# CrowPanel_Pico_Display-2_8_V1_0_240412.net
KiCad netlist of a schematic drawn in EAGLE
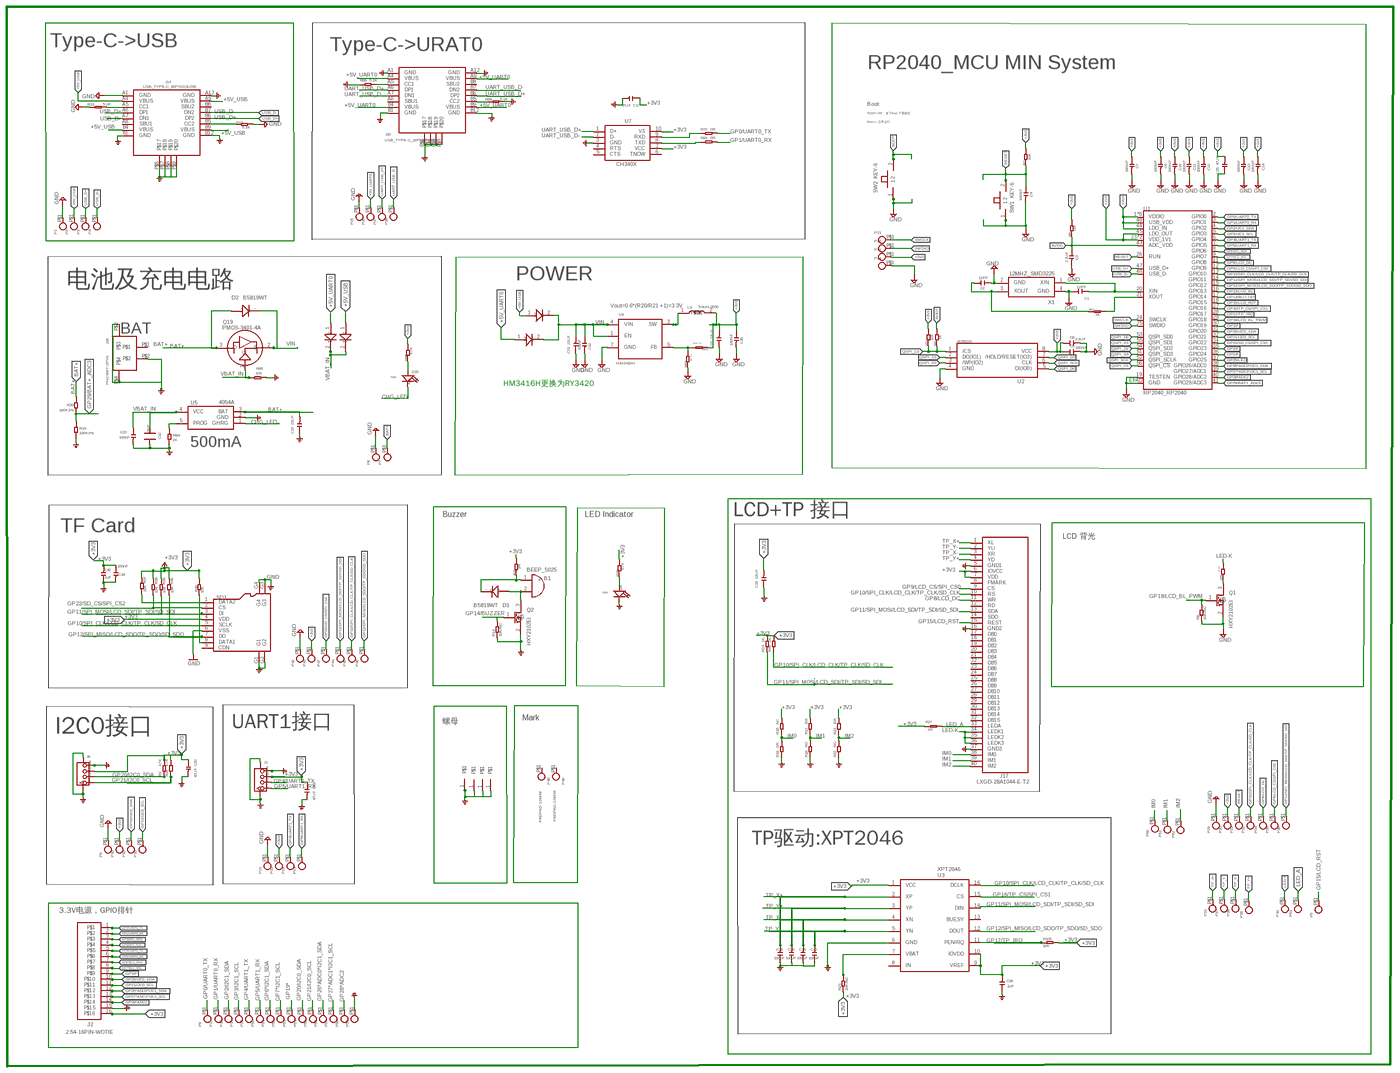
[diagram p0: schematic, sheet 1, overview]
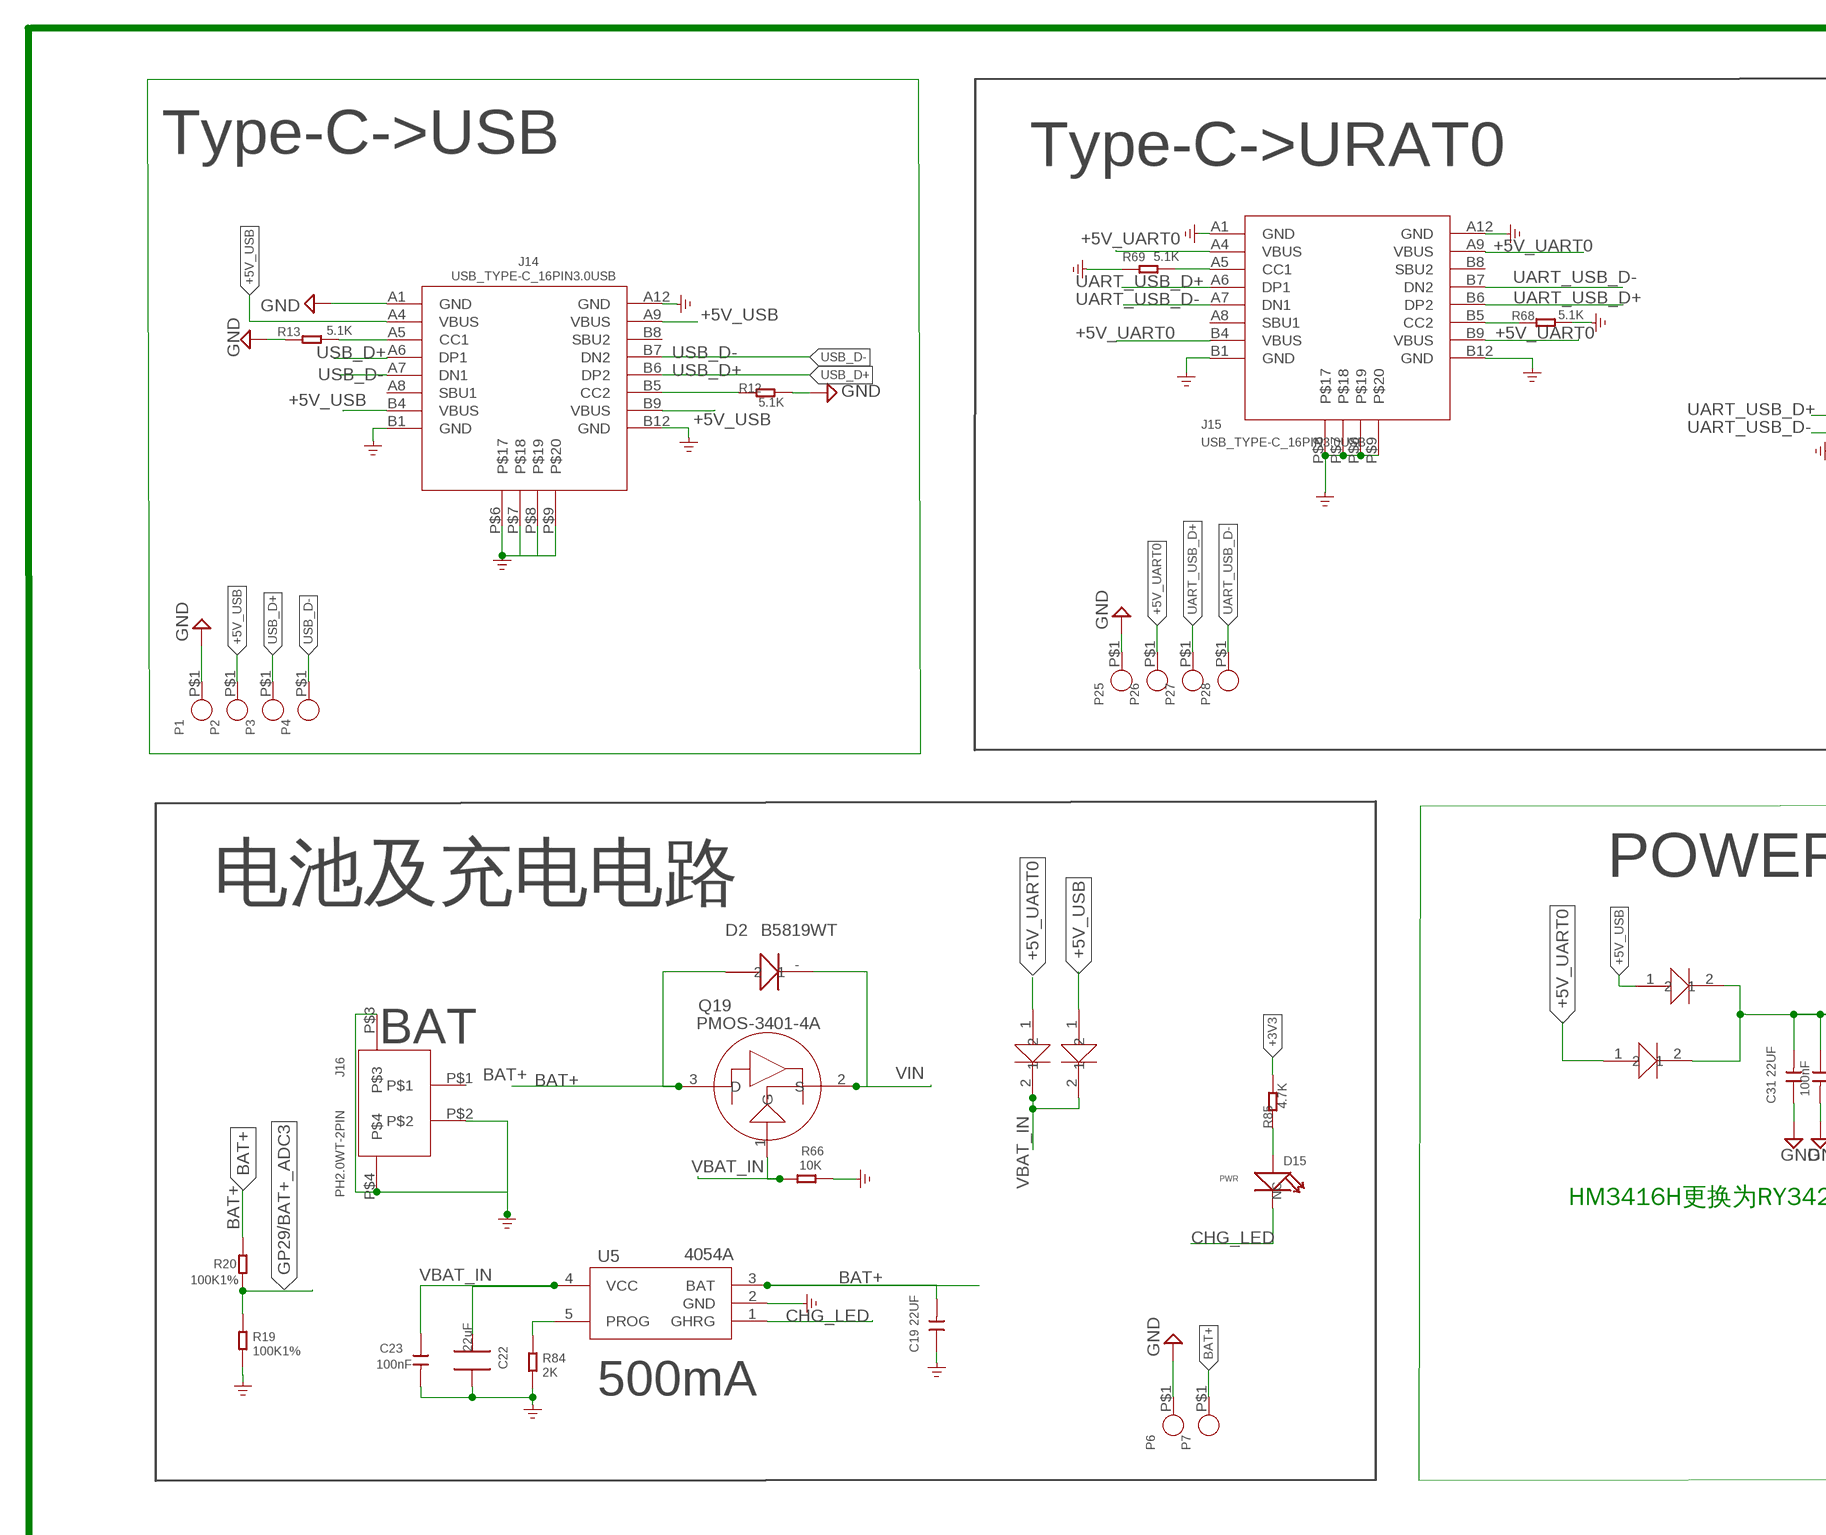
[diagram p1: schematic, sheet 1, part 1 of 4]
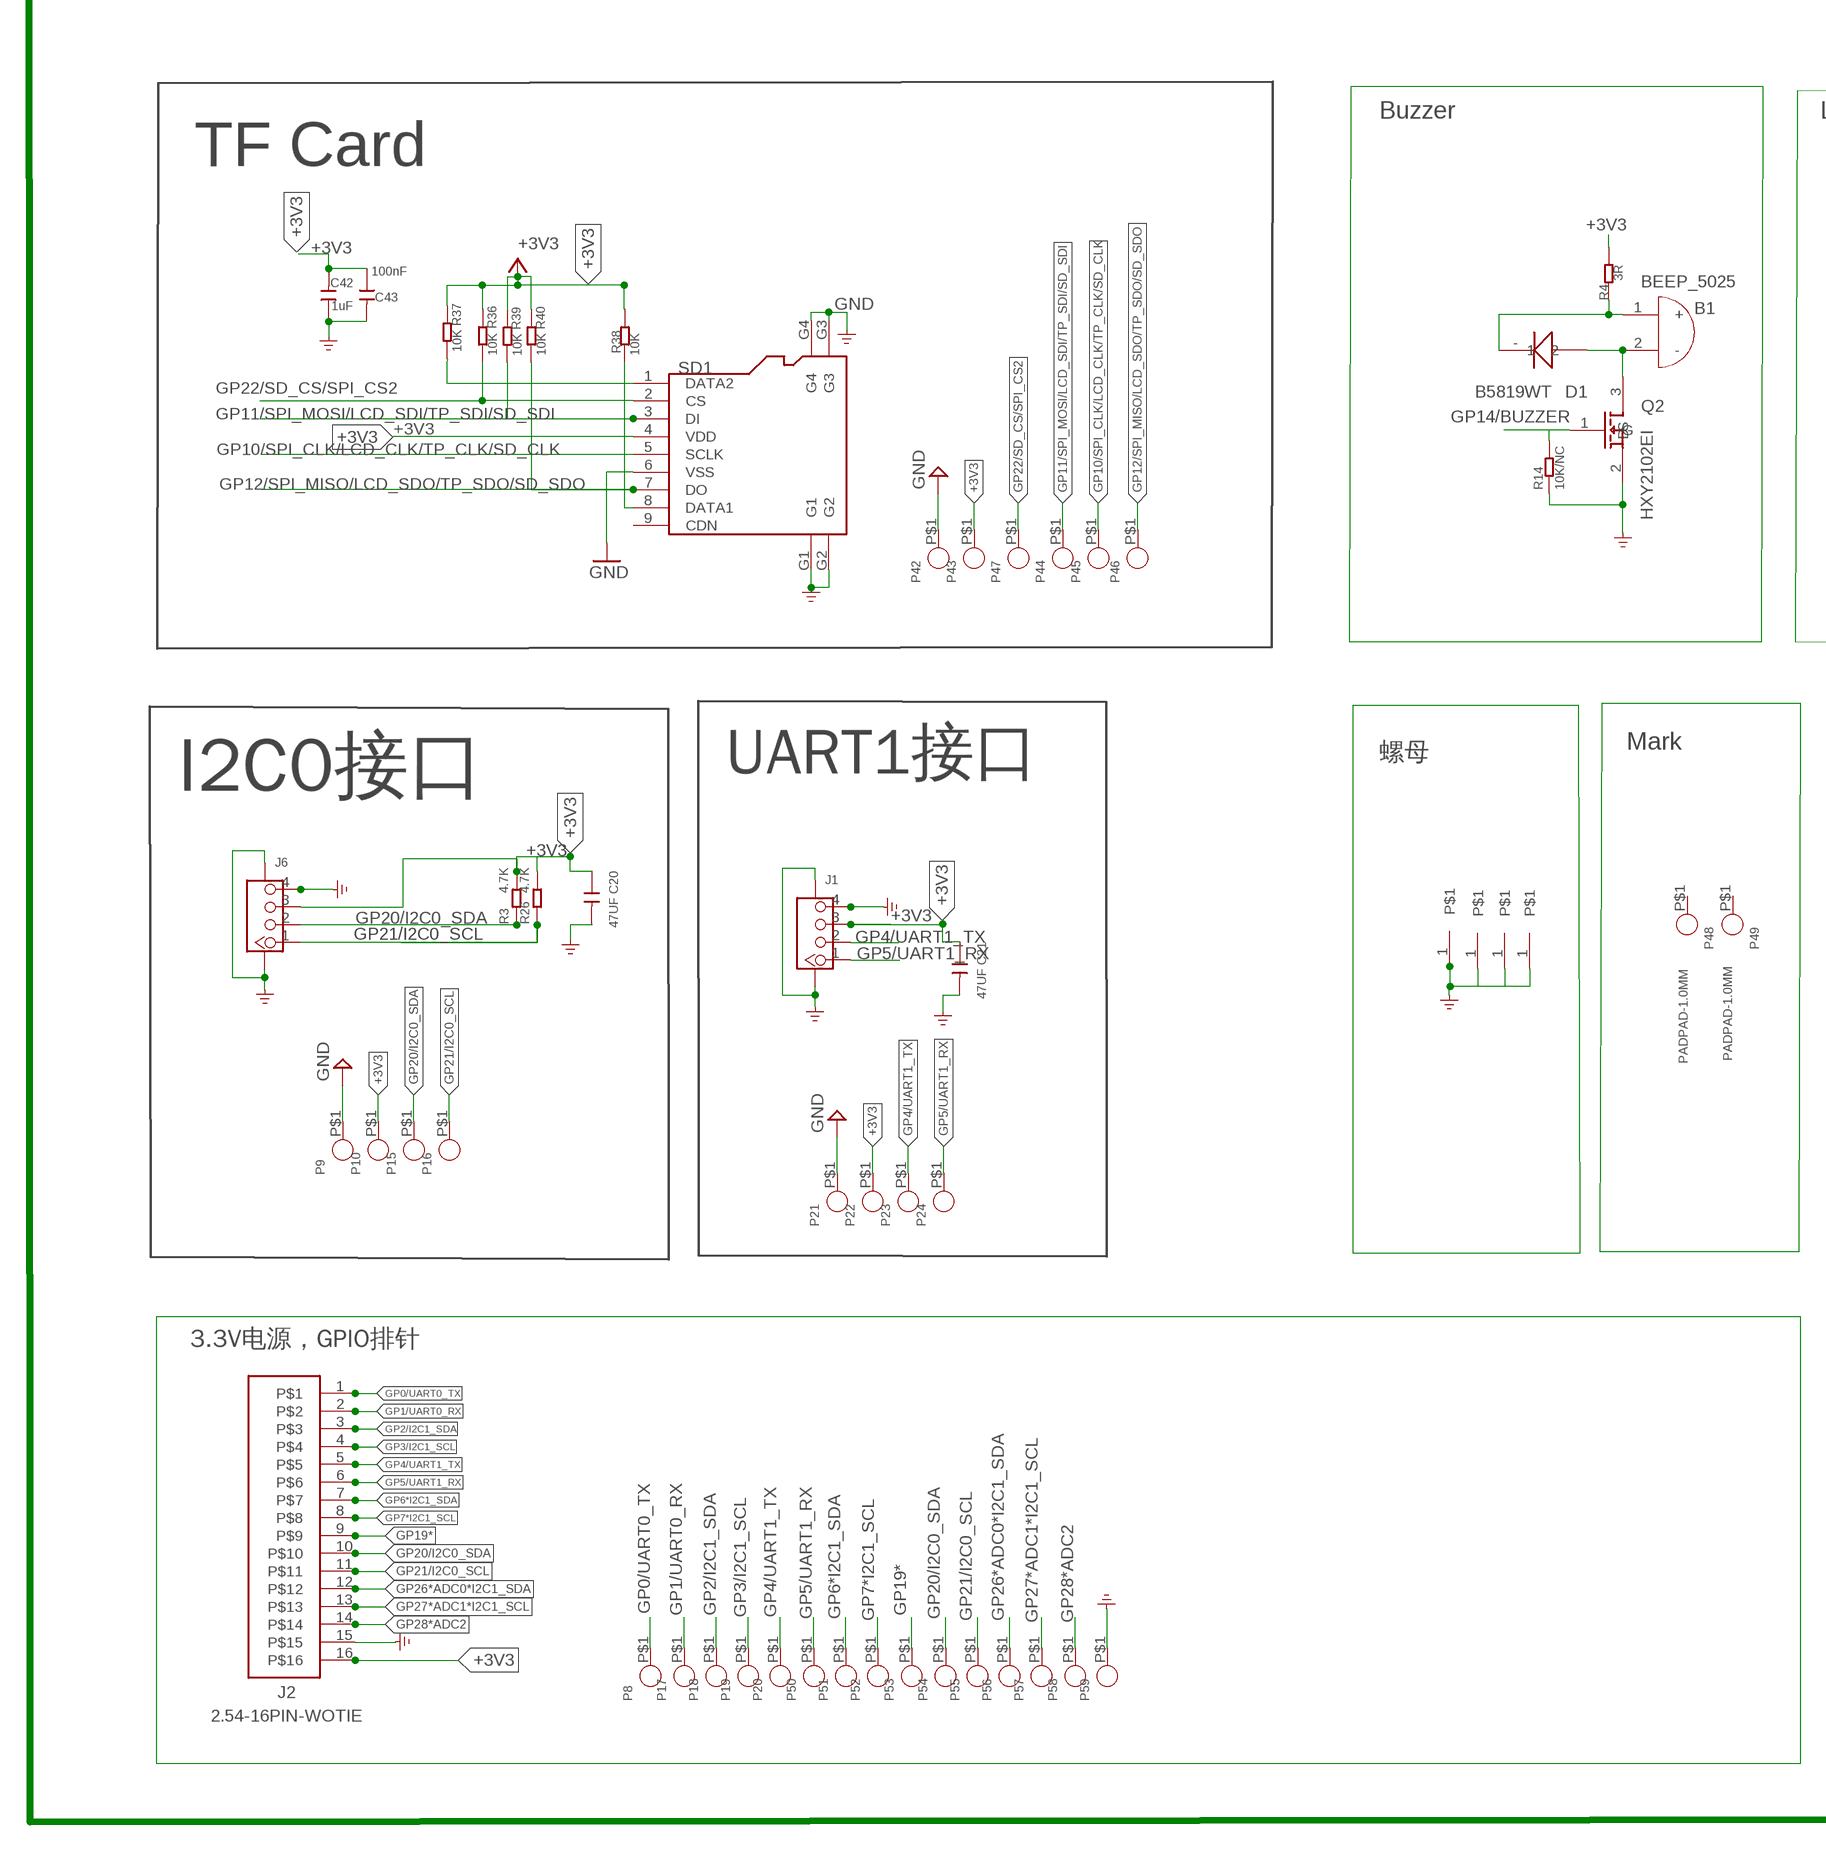
[diagram p2: schematic, sheet 1, part 2 of 4]
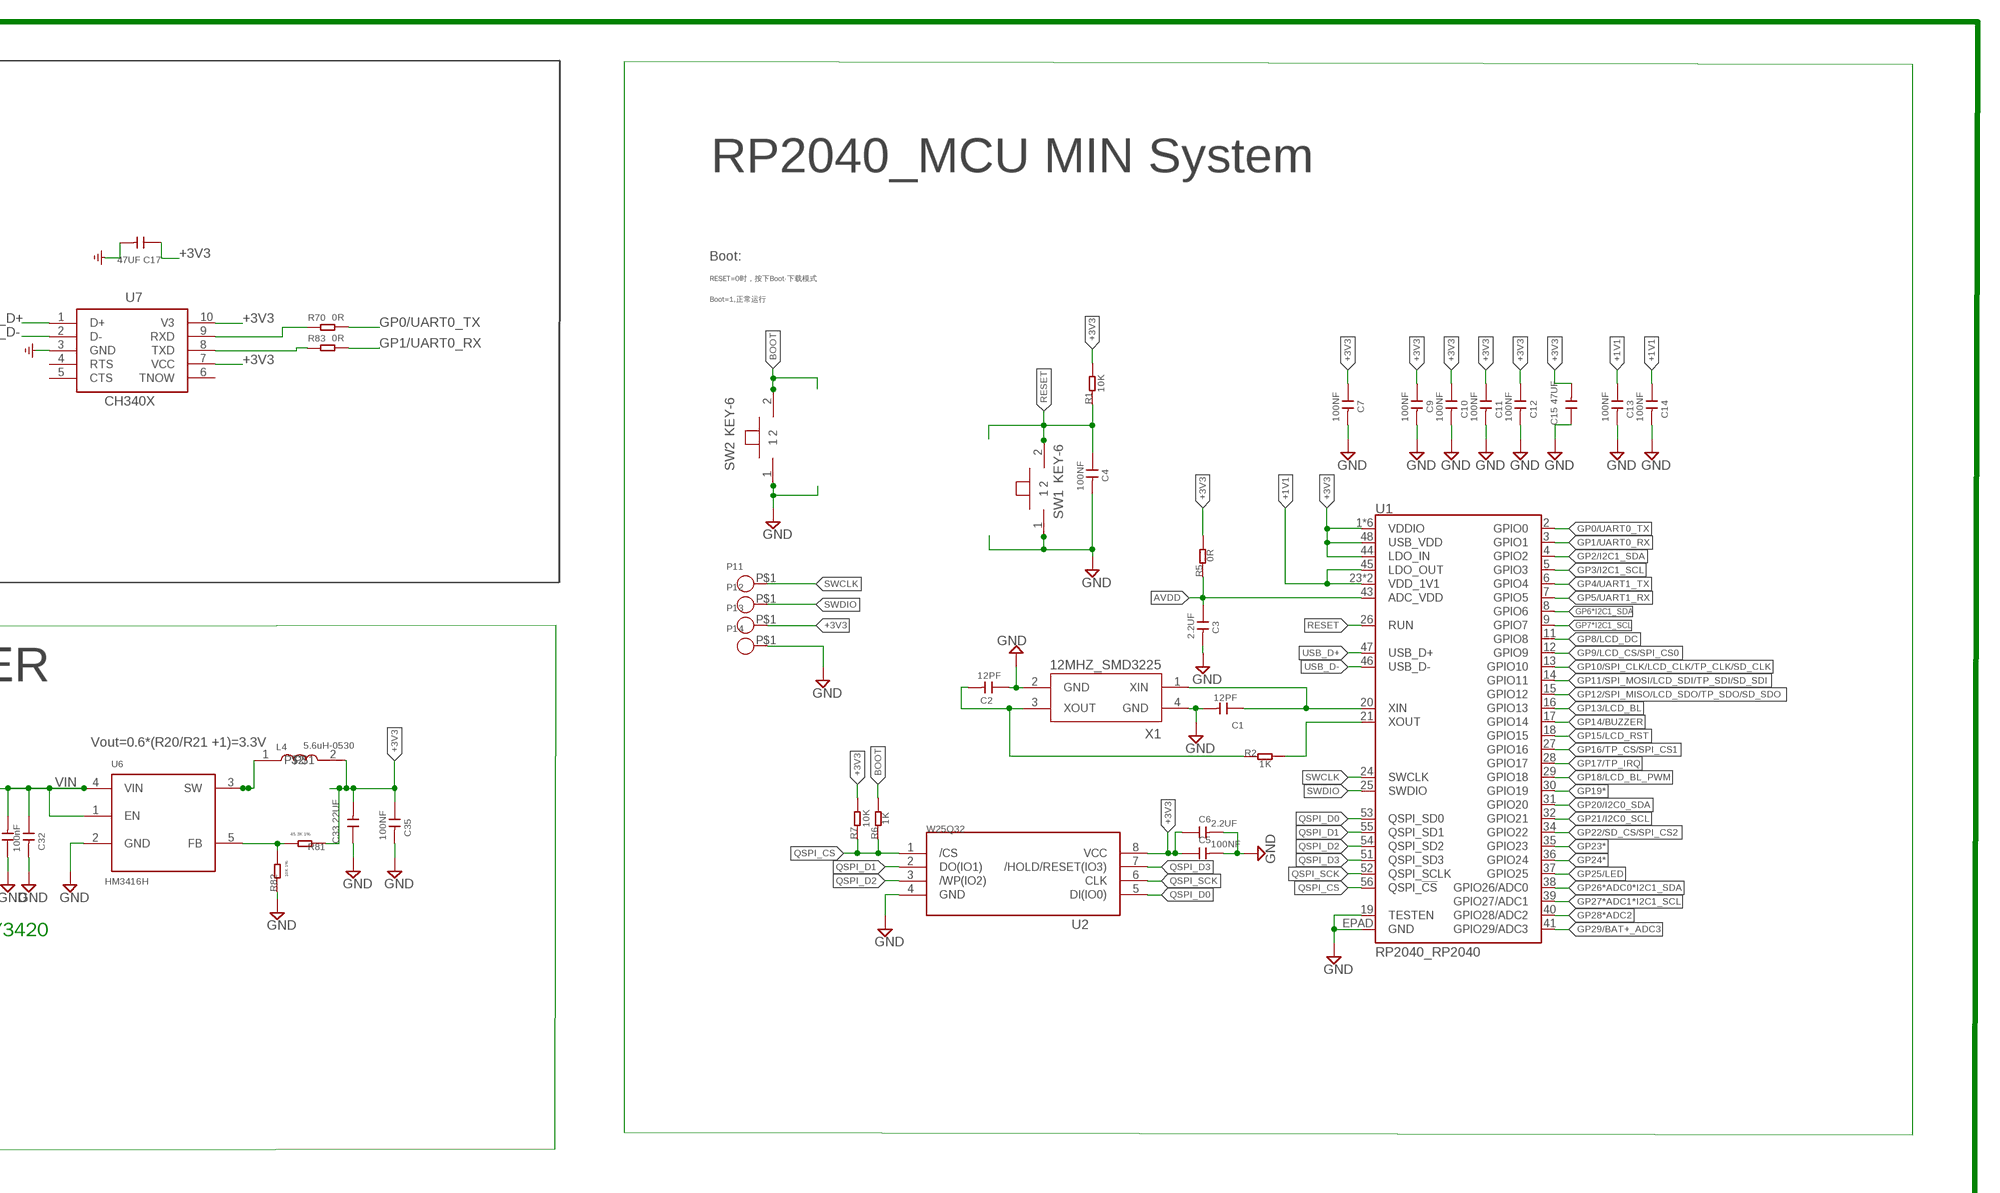
[diagram p3: schematic, sheet 1, part 3 of 4]
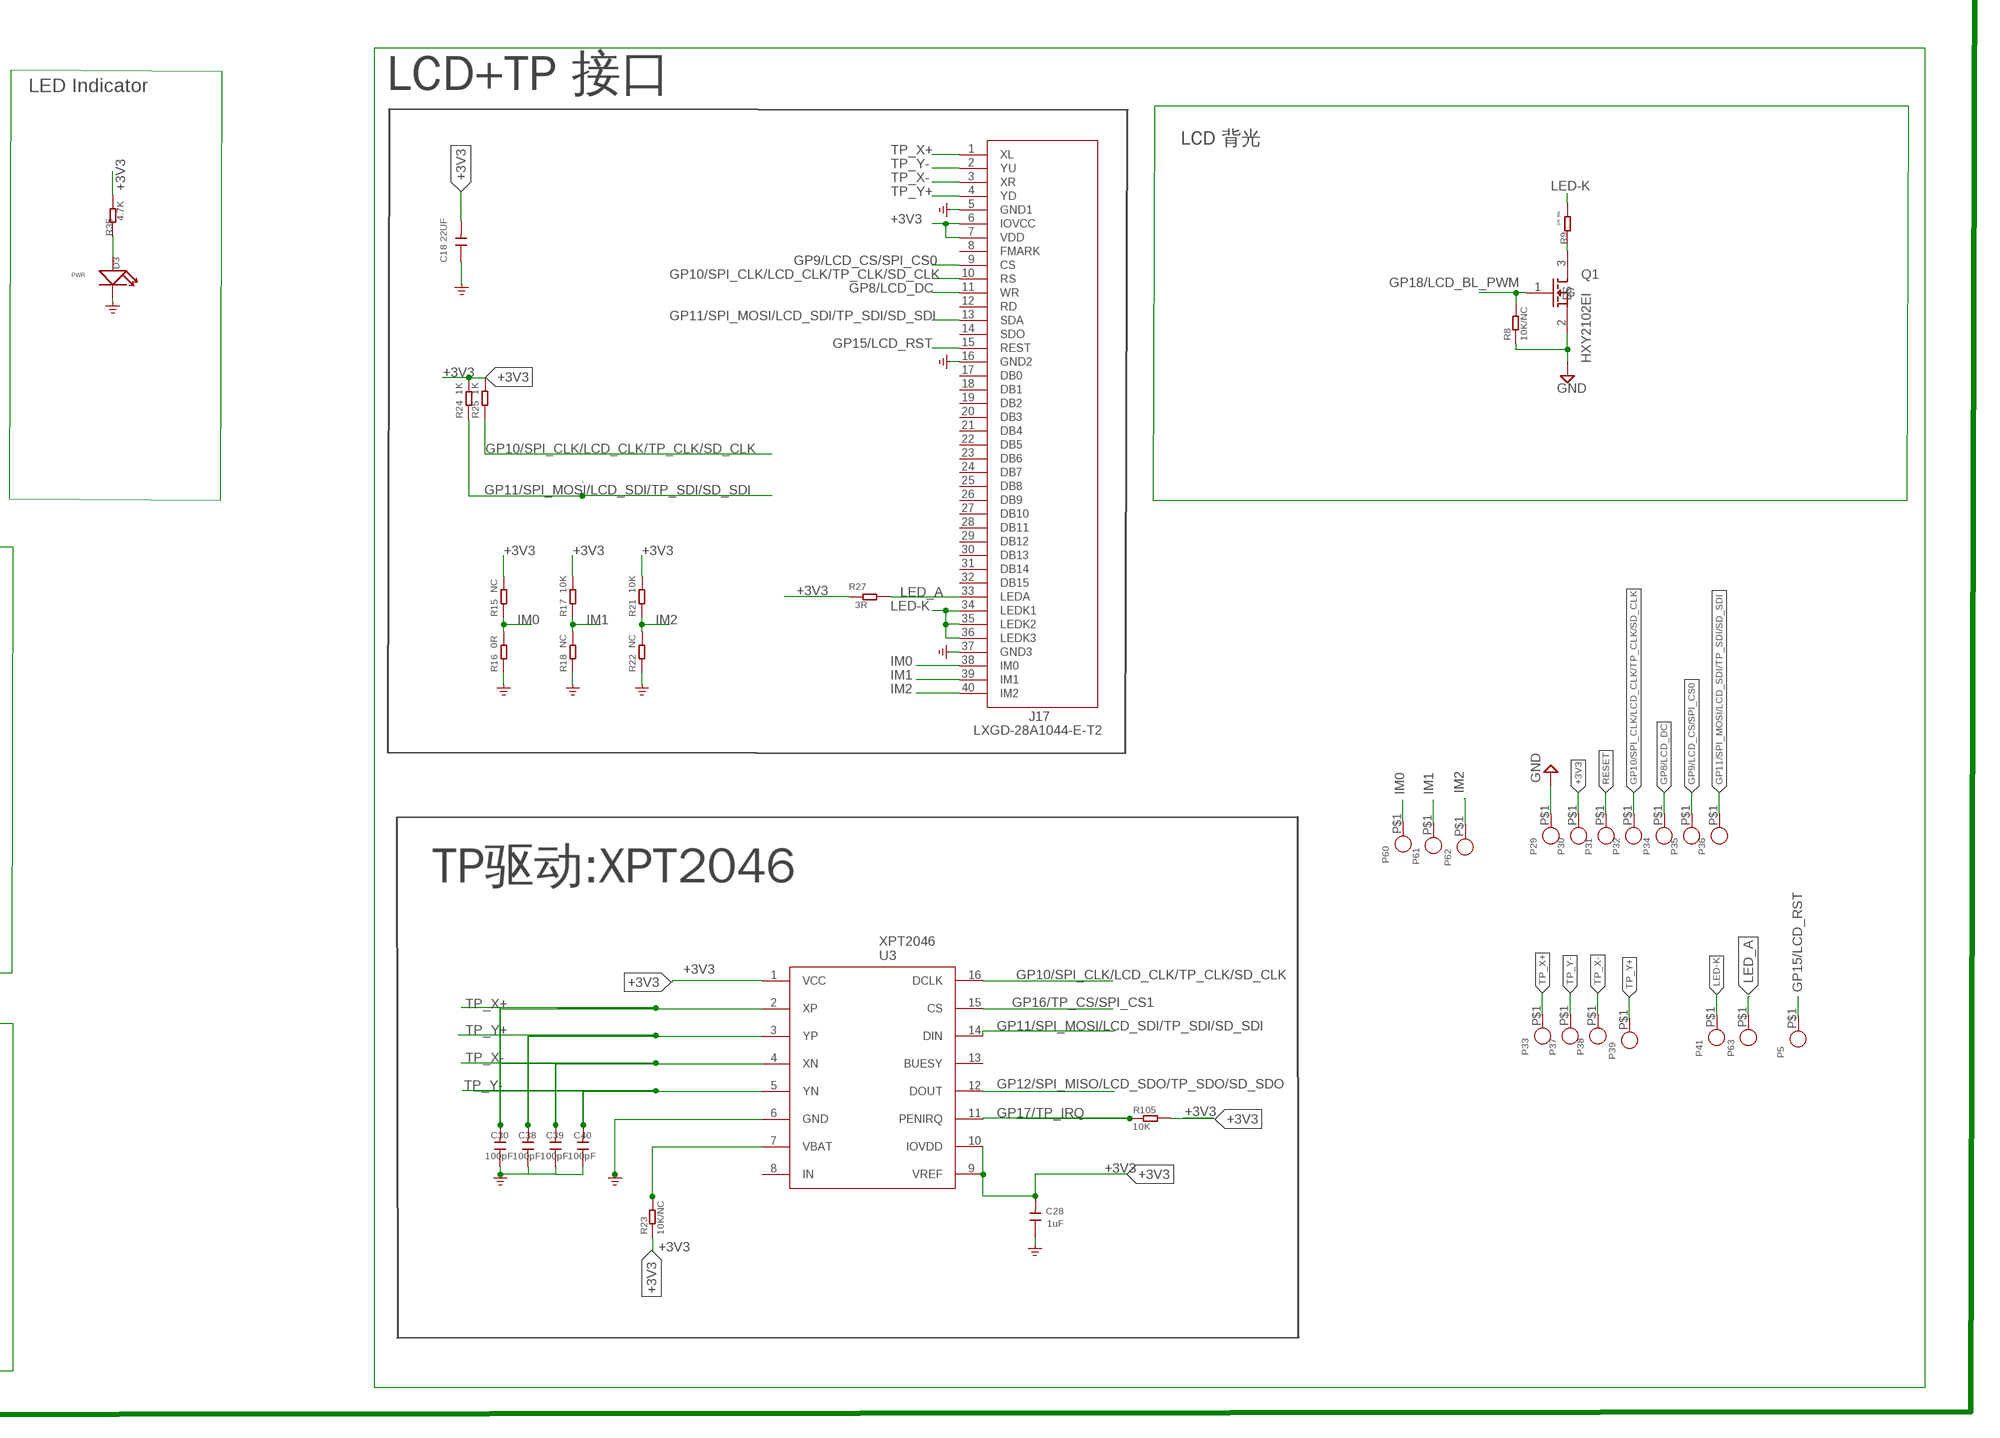
[diagram p4: schematic, sheet 1, part 4 of 4]

(export (version "E")
  (design (tool "Eeschema 10.0.6"))
  (components
    (comp (ref "B1")
      (value "BEEP_5025")
      (footprint "eagle-import:BEEP_5025")
      (libsource (lib "eagle-import") (part "BEEP_5025"))
    )
    (comp (ref "C1")
      (value "12PF")
      (footprint "eagle-import:A_XBJ_0603")
      (libsource (lib "eagle-import") (part "A_XBJ_C0603"))
    )
    (comp (ref "C2")
      (value "12PF")
      (footprint "eagle-import:A_XBJ_0603")
      (libsource (lib "eagle-import") (part "A_XBJ_C0603"))
    )
    (comp (ref "C3")
      (value "2.2UF")
      (footprint "eagle-import:A_XBJ_0603")
      (libsource (lib "eagle-import") (part "A_XBJ_C0603"))
    )
    (comp (ref "C4")
      (value "100NF")
      (footprint "eagle-import:A_XBJ_0603")
      (libsource (lib "eagle-import") (part "A_XBJ_C0603"))
    )
    (comp (ref "C5")
      (value "100NF")
      (footprint "eagle-import:A_XBJ_0603")
      (libsource (lib "eagle-import") (part "A_XBJ_C0603"))
    )
    (comp (ref "C6")
      (value "2.2UF")
      (footprint "eagle-import:A_XBJ_0603")
      (libsource (lib "eagle-import") (part "A_XBJ_C0603"))
    )
    (comp (ref "C7")
      (value "100NF")
      (footprint "eagle-import:A_XBJ_0603")
      (libsource (lib "eagle-import") (part "A_XBJ_C0603"))
    )
    (comp (ref "C9")
      (value "100NF")
      (footprint "eagle-import:A_XBJ_0603")
      (libsource (lib "eagle-import") (part "A_XBJ_C0603"))
    )
    (comp (ref "C10")
      (value "100NF")
      (footprint "eagle-import:A_XBJ_0603")
      (libsource (lib "eagle-import") (part "A_XBJ_C0603"))
    )
    (comp (ref "C11")
      (value "100NF")
      (footprint "eagle-import:A_XBJ_0603")
      (libsource (lib "eagle-import") (part "A_XBJ_C0603"))
    )
    (comp (ref "C12")
      (value "100NF")
      (footprint "eagle-import:A_XBJ_0603")
      (libsource (lib "eagle-import") (part "A_XBJ_C0603"))
    )
    (comp (ref "C13")
      (value "100NF")
      (footprint "eagle-import:A_XBJ_0603")
      (libsource (lib "eagle-import") (part "A_XBJ_C0603"))
    )
    (comp (ref "C14")
      (value "100NF")
      (footprint "eagle-import:A_XBJ_0603")
      (libsource (lib "eagle-import") (part "A_XBJ_C0603"))
    )
    (comp (ref "C15")
      (value "47UF")
      (footprint "eagle-import:A_XBJ_0805")
      (libsource (lib "eagle-import") (part "A_XBJ_C0805"))
    )
    (comp (ref "C17")
      (value "47UF")
      (footprint "eagle-import:A_XBJ_0805")
      (libsource (lib "eagle-import") (part "A_XBJ_C0805"))
    )
    (comp (ref "C18")
      (value "22UF")
      (footprint "eagle-import:A_XBJ_0805")
      (libsource (lib "eagle-import") (part "A_XBJ_C0805"))
    )
    (comp (ref "C19")
      (value "22UF")
      (footprint "eagle-import:A_XBJ_0805")
      (libsource (lib "eagle-import") (part "A_XBJ_C0805"))
    )
    (comp (ref "C20")
      (value "47UF")
      (footprint "eagle-import:A_XBJ_0805")
      (libsource (lib "eagle-import") (part "A_XBJ_C0805"))
    )
    (comp (ref "C21")
      (value "47UF")
      (footprint "eagle-import:A_XBJ_0805")
      (libsource (lib "eagle-import") (part "A_XBJ_C0805"))
    )
    (comp (ref "C22")
      (value "22uF")
      (footprint "eagle-import:0805_S")
      (libsource (lib "eagle-import") (part "C0805_S"))
    )
    (comp (ref "C23")
      (value "100nF")
      (footprint "eagle-import:C0603")
      (libsource (lib "eagle-import") (part "C-0603"))
    )
    (comp (ref "C28")
      (value "1uF")
      (footprint "eagle-import:DISCRETE_C0603")
      (libsource (lib "eagle-import") (part "DISCRETE_C-0603"))
    )
    (comp (ref "C30")
      (value "100pF")
      (footprint "eagle-import:0603")
      (libsource (lib "eagle-import") (part "C0603"))
    )
    (comp (ref "C31")
      (value "22UF")
      (footprint "eagle-import:A_XBJ_0805")
      (libsource (lib "eagle-import") (part "A_XBJ_C0805"))
    )
    (comp (ref "C32")
      (value "100nF")
      (footprint "eagle-import:A_XBJ_0603")
      (libsource (lib "eagle-import") (part "A_XBJ_C0603"))
    )
    (comp (ref "C33")
      (value "22UF")
      (footprint "eagle-import:A_XBJ_0805")
      (libsource (lib "eagle-import") (part "A_XBJ_C0805"))
    )
    (comp (ref "C35")
      (value "100NF")
      (footprint "eagle-import:A_XBJ_0603")
      (libsource (lib "eagle-import") (part "A_XBJ_C0603"))
    )
    (comp (ref "C38")
      (value "100pF")
      (footprint "eagle-import:0603")
      (libsource (lib "eagle-import") (part "C0603"))
    )
    (comp (ref "C39")
      (value "100pF")
      (footprint "eagle-import:0603")
      (libsource (lib "eagle-import") (part "C0603"))
    )
    (comp (ref "C40")
      (value "100pF")
      (footprint "eagle-import:0603")
      (libsource (lib "eagle-import") (part "C0603"))
    )
    (comp (ref "C42")
      (value "1uF")
      (footprint "eagle-import:DISCRETE_C0603")
      (libsource (lib "eagle-import") (part "DISCRETE_C-0603"))
    )
    (comp (ref "C43")
      (value "100nF")
      (footprint "eagle-import:C0603")
      (libsource (lib "eagle-import") (part "C-0603"))
    )
    (comp (ref "D1")
      (value "B5819WT")
      (footprint "eagle-import:SOD-523")
      (libsource (lib "eagle-import") (part "DIODE_W"))
    )
    (comp (ref "D2")
      (value "B5819WT")
      (footprint "eagle-import:SOD-523")
      (libsource (lib "eagle-import") (part "DIODE_W"))
    )
    (comp (ref "D3")
      (value "DISCRETE_007-LED0603")
      (footprint "eagle-import:DISCRETE_D0603")
      (libsource (lib "eagle-import") (part "DISCRETE_007-LED0603"))
    )
    (comp (ref "D4")
      (value "SOD-323")
      (footprint "eagle-import:SOD-323")
      (libsource (lib "eagle-import") (part "SOD-323"))
    )
    (comp (ref "D5")
      (value "SOD-323")
      (footprint "eagle-import:SOD-323")
      (libsource (lib "eagle-import") (part "SOD-323"))
    )
    (comp (ref "D6")
      (value "SOD-323")
      (footprint "eagle-import:SOD-323")
      (libsource (lib "eagle-import") (part "SOD-323"))
    )
    (comp (ref "D8")
      (value "SOD-323")
      (footprint "eagle-import:SOD-323")
      (libsource (lib "eagle-import") (part "SOD-323"))
    )
    (comp (ref "D15")
      (value "NC")
      (footprint "eagle-import:DISCRETE_D0603")
      (libsource (lib "eagle-import") (part "DISCRETE_007-LED0603"))
    )
    (comp (ref "J1")
      (value "CONNECTOR_TWIG-4P-2.0-SMD-FEMALE-REINFORCE90D")
      (footprint "eagle-import:CONNECTOR_4P-SMD-2.0-90D")
      (libsource (lib "eagle-import") (part "CONNECTOR_TWIG-4P-2.0-SMD-FEMALE-REINFORCE90D"))
    )
    (comp (ref "J2")
      (value "2.54-16PIN-WOTIE")
      (footprint "eagle-import:2.54-16P-WOTIE")
      (libsource (lib "eagle-import") (part "2.54-16PIN-WOTIE"))
    )
    (comp (ref "J6")
      (value "CONNECTOR_TWIG-4P-2.0-SMD-FEMALE-REINFORCE90D")
      (footprint "eagle-import:CONNECTOR_4P-SMD-2.0-90D")
      (libsource (lib "eagle-import") (part "CONNECTOR_TWIG-4P-2.0-SMD-FEMALE-REINFORCE90D"))
    )
    (comp (ref "J14")
      (value "USB_TYPE-C_16PIN3.0USB")
      (footprint "eagle-import:KEVIN_3.0TYPEC-SMD")
      (libsource (lib "eagle-import") (part "USB_TYPE-C_16PIN3.0USB"))
    )
    (comp (ref "J15")
      (value "USB_TYPE-C_16PIN3.0USB")
      (footprint "eagle-import:KEVIN_3.0TYPEC-SMD")
      (libsource (lib "eagle-import") (part "USB_TYPE-C_16PIN3.0USB"))
    )
    (comp (ref "J16")
      (value "PH2.0WT-2PIN")
      (footprint "eagle-import:PH2.0WT-2PIN")
      (libsource (lib "eagle-import") (part "PH2.0WT-2PIN"))
    )
    (comp (ref "J17")
      (value "LXGD-28A1044-E-T2")
      (footprint "eagle-import:40PIN-0.5MM")
      (libsource (lib "eagle-import") (part "LXGD-28A1044-E-T2"))
    )
    (comp (ref "L4")
      (value "5.6uH-0530")
      (footprint "eagle-import:CD54_CD54")
      (libsource (lib "eagle-import") (part "L-0530"))
    )
    (comp (ref "P1")
      (value "CROWPI_POW_PADPAD-1.0MM")
      (footprint "eagle-import:CROWPI_POW_PAD-1.0MM")
      (libsource (lib "eagle-import") (part "CROWPI_POW_PADPAD-1.0MM"))
    )
    (comp (ref "P2")
      (value "CROWPI_POW_PADPAD-1.0MM")
      (footprint "eagle-import:CROWPI_POW_PAD-1.0MM")
      (libsource (lib "eagle-import") (part "CROWPI_POW_PADPAD-1.0MM"))
    )
    (comp (ref "P3")
      (value "CROWPI_POW_PADPAD-1.0MM")
      (footprint "eagle-import:CROWPI_POW_PAD-1.0MM")
      (libsource (lib "eagle-import") (part "CROWPI_POW_PADPAD-1.0MM"))
    )
    (comp (ref "P4")
      (value "CROWPI_POW_PADPAD-1.0MM")
      (footprint "eagle-import:CROWPI_POW_PAD-1.0MM")
      (libsource (lib "eagle-import") (part "CROWPI_POW_PADPAD-1.0MM"))
    )
    (comp (ref "P5")
      (value "CROWPI_POW_PADPAD-1.0MM")
      (footprint "eagle-import:CROWPI_POW_PAD-1.0MM")
      (libsource (lib "eagle-import") (part "CROWPI_POW_PADPAD-1.0MM"))
    )
    (comp (ref "P6")
      (value "CROWPI_POW_PADPAD-1.0MM")
      (footprint "eagle-import:CROWPI_POW_PAD-1.0MM")
      (libsource (lib "eagle-import") (part "CROWPI_POW_PADPAD-1.0MM"))
    )
    (comp (ref "P7")
      (value "CROWPI_POW_PADPAD-1.0MM")
      (footprint "eagle-import:CROWPI_POW_PAD-1.0MM")
      (libsource (lib "eagle-import") (part "CROWPI_POW_PADPAD-1.0MM"))
    )
    (comp (ref "P8")
      (value "CROWPI_POW_PADPAD-1.0MM")
      (footprint "eagle-import:CROWPI_POW_PAD-1.0MM")
      (libsource (lib "eagle-import") (part "CROWPI_POW_PADPAD-1.0MM"))
    )
    (comp (ref "P9")
      (value "CROWPI_POW_PADPAD-1.0MM")
      (footprint "eagle-import:CROWPI_POW_PAD-1.0MM")
      (libsource (lib "eagle-import") (part "CROWPI_POW_PADPAD-1.0MM"))
    )
    (comp (ref "P10")
      (value "CROWPI_POW_PADPAD-1.0MM")
      (footprint "eagle-import:CROWPI_POW_PAD-1.0MM")
      (libsource (lib "eagle-import") (part "CROWPI_POW_PADPAD-1.0MM"))
    )
    (comp (ref "P11")
      (value "CROWPI_POW_PADPAD-1.0MM")
      (footprint "eagle-import:CROWPI_POW_PAD-1.0MM")
      (libsource (lib "eagle-import") (part "CROWPI_POW_PADPAD-1.0MM"))
    )
    (comp (ref "P12")
      (value "CROWPI_POW_PADPAD-1.0MM")
      (footprint "eagle-import:CROWPI_POW_PAD-1.0MM")
      (libsource (lib "eagle-import") (part "CROWPI_POW_PADPAD-1.0MM"))
    )
    (comp (ref "P13")
      (value "CROWPI_POW_PADPAD-1.0MM")
      (footprint "eagle-import:CROWPI_POW_PAD-1.0MM")
      (libsource (lib "eagle-import") (part "CROWPI_POW_PADPAD-1.0MM"))
    )
    (comp (ref "P14")
      (value "CROWPI_POW_PADPAD-1.0MM")
      (footprint "eagle-import:CROWPI_POW_PAD-1.0MM")
      (libsource (lib "eagle-import") (part "CROWPI_POW_PADPAD-1.0MM"))
    )
    (comp (ref "P15")
      (value "CROWPI_POW_PADPAD-1.0MM")
      (footprint "eagle-import:CROWPI_POW_PAD-1.0MM")
      (libsource (lib "eagle-import") (part "CROWPI_POW_PADPAD-1.0MM"))
    )
    (comp (ref "P16")
      (value "CROWPI_POW_PADPAD-1.0MM")
      (footprint "eagle-import:CROWPI_POW_PAD-1.0MM")
      (libsource (lib "eagle-import") (part "CROWPI_POW_PADPAD-1.0MM"))
    )
    (comp (ref "P17")
      (value "CROWPI_POW_PADPAD-1.0MM")
      (footprint "eagle-import:CROWPI_POW_PAD-1.0MM")
      (libsource (lib "eagle-import") (part "CROWPI_POW_PADPAD-1.0MM"))
    )
    (comp (ref "P18")
      (value "CROWPI_POW_PADPAD-1.0MM")
      (footprint "eagle-import:CROWPI_POW_PAD-1.0MM")
      (libsource (lib "eagle-import") (part "CROWPI_POW_PADPAD-1.0MM"))
    )
    (comp (ref "P19")
      (value "CROWPI_POW_PADPAD-1.0MM")
      (footprint "eagle-import:CROWPI_POW_PAD-1.0MM")
      (libsource (lib "eagle-import") (part "CROWPI_POW_PADPAD-1.0MM"))
    )
    (comp (ref "P20")
      (value "CROWPI_POW_PADPAD-1.0MM")
      (footprint "eagle-import:CROWPI_POW_PAD-1.0MM")
      (libsource (lib "eagle-import") (part "CROWPI_POW_PADPAD-1.0MM"))
    )
    (comp (ref "P21")
      (value "CROWPI_POW_PADPAD-1.0MM")
      (footprint "eagle-import:CROWPI_POW_PAD-1.0MM")
      (libsource (lib "eagle-import") (part "CROWPI_POW_PADPAD-1.0MM"))
    )
    (comp (ref "P22")
      (value "CROWPI_POW_PADPAD-1.0MM")
      (footprint "eagle-import:CROWPI_POW_PAD-1.0MM")
      (libsource (lib "eagle-import") (part "CROWPI_POW_PADPAD-1.0MM"))
    )
    (comp (ref "P23")
      (value "CROWPI_POW_PADPAD-1.0MM")
      (footprint "eagle-import:CROWPI_POW_PAD-1.0MM")
      (libsource (lib "eagle-import") (part "CROWPI_POW_PADPAD-1.0MM"))
    )
    (comp (ref "P24")
      (value "CROWPI_POW_PADPAD-1.0MM")
      (footprint "eagle-import:CROWPI_POW_PAD-1.0MM")
      (libsource (lib "eagle-import") (part "CROWPI_POW_PADPAD-1.0MM"))
    )
    (comp (ref "P25")
      (value "CROWPI_POW_PADPAD-1.0MM")
      (footprint "eagle-import:CROWPI_POW_PAD-1.0MM")
      (libsource (lib "eagle-import") (part "CROWPI_POW_PADPAD-1.0MM"))
    )
    (comp (ref "P26")
      (value "CROWPI_POW_PADPAD-1.0MM")
      (footprint "eagle-import:CROWPI_POW_PAD-1.0MM")
      (libsource (lib "eagle-import") (part "CROWPI_POW_PADPAD-1.0MM"))
    )
    (comp (ref "P27")
      (value "CROWPI_POW_PADPAD-1.0MM")
      (footprint "eagle-import:CROWPI_POW_PAD-1.0MM")
      (libsource (lib "eagle-import") (part "CROWPI_POW_PADPAD-1.0MM"))
    )
    (comp (ref "P28")
      (value "CROWPI_POW_PADPAD-1.0MM")
      (footprint "eagle-import:CROWPI_POW_PAD-1.0MM")
      (libsource (lib "eagle-import") (part "CROWPI_POW_PADPAD-1.0MM"))
    )
    (comp (ref "P29")
      (value "CROWPI_POW_PADPAD-1.0MM")
      (footprint "eagle-import:CROWPI_POW_PAD-1.0MM")
      (libsource (lib "eagle-import") (part "CROWPI_POW_PADPAD-1.0MM"))
    )
    (comp (ref "P30")
      (value "CROWPI_POW_PADPAD-1.0MM")
      (footprint "eagle-import:CROWPI_POW_PAD-1.0MM")
      (libsource (lib "eagle-import") (part "CROWPI_POW_PADPAD-1.0MM"))
    )
    (comp (ref "P31")
      (value "CROWPI_POW_PADPAD-1.0MM")
      (footprint "eagle-import:CROWPI_POW_PAD-1.0MM")
      (libsource (lib "eagle-import") (part "CROWPI_POW_PADPAD-1.0MM"))
    )
    (comp (ref "P32")
      (value "CROWPI_POW_PADPAD-1.0MM")
      (footprint "eagle-import:CROWPI_POW_PAD-1.0MM")
      (libsource (lib "eagle-import") (part "CROWPI_POW_PADPAD-1.0MM"))
    )
    (comp (ref "P33")
      (value "CROWPI_POW_PADPAD-1.0MM")
      (footprint "eagle-import:CROWPI_POW_PAD-1.0MM")
      (libsource (lib "eagle-import") (part "CROWPI_POW_PADPAD-1.0MM"))
    )
    (comp (ref "P34")
      (value "CROWPI_POW_PADPAD-1.0MM")
      (footprint "eagle-import:CROWPI_POW_PAD-1.0MM")
      (libsource (lib "eagle-import") (part "CROWPI_POW_PADPAD-1.0MM"))
    )
    (comp (ref "P35")
      (value "CROWPI_POW_PADPAD-1.0MM")
      (footprint "eagle-import:CROWPI_POW_PAD-1.0MM")
      (libsource (lib "eagle-import") (part "CROWPI_POW_PADPAD-1.0MM"))
    )
    (comp (ref "P36")
      (value "CROWPI_POW_PADPAD-1.0MM")
      (footprint "eagle-import:CROWPI_POW_PAD-1.0MM")
      (libsource (lib "eagle-import") (part "CROWPI_POW_PADPAD-1.0MM"))
    )
    (comp (ref "P37")
      (value "CROWPI_POW_PADPAD-1.0MM")
      (footprint "eagle-import:CROWPI_POW_PAD-1.0MM")
      (libsource (lib "eagle-import") (part "CROWPI_POW_PADPAD-1.0MM"))
    )
    (comp (ref "P38")
      (value "CROWPI_POW_PADPAD-1.0MM")
      (footprint "eagle-import:CROWPI_POW_PAD-1.0MM")
      (libsource (lib "eagle-import") (part "CROWPI_POW_PADPAD-1.0MM"))
    )
    (comp (ref "P39")
      (value "CROWPI_POW_PADPAD-1.0MM")
      (footprint "eagle-import:CROWPI_POW_PAD-1.0MM")
      (libsource (lib "eagle-import") (part "CROWPI_POW_PADPAD-1.0MM"))
    )
    (comp (ref "P41")
      (value "CROWPI_POW_PADPAD-1.0MM")
      (footprint "eagle-import:CROWPI_POW_PAD-1.0MM")
      (libsource (lib "eagle-import") (part "CROWPI_POW_PADPAD-1.0MM"))
    )
    (comp (ref "P42")
      (value "CROWPI_POW_PADPAD-1.0MM")
      (footprint "eagle-import:CROWPI_POW_PAD-1.0MM")
      (libsource (lib "eagle-import") (part "CROWPI_POW_PADPAD-1.0MM"))
    )
    (comp (ref "P43")
      (value "CROWPI_POW_PADPAD-1.0MM")
      (footprint "eagle-import:CROWPI_POW_PAD-1.0MM")
      (libsource (lib "eagle-import") (part "CROWPI_POW_PADPAD-1.0MM"))
    )
    (comp (ref "P44")
      (value "CROWPI_POW_PADPAD-1.0MM")
      (footprint "eagle-import:CROWPI_POW_PAD-1.0MM")
      (libsource (lib "eagle-import") (part "CROWPI_POW_PADPAD-1.0MM"))
    )
    (comp (ref "P45")
      (value "CROWPI_POW_PADPAD-1.0MM")
      (footprint "eagle-import:CROWPI_POW_PAD-1.0MM")
      (libsource (lib "eagle-import") (part "CROWPI_POW_PADPAD-1.0MM"))
    )
    (comp (ref "P46")
      (value "CROWPI_POW_PADPAD-1.0MM")
      (footprint "eagle-import:CROWPI_POW_PAD-1.0MM")
      (libsource (lib "eagle-import") (part "CROWPI_POW_PADPAD-1.0MM"))
    )
    (comp (ref "P47")
      (value "CROWPI_POW_PADPAD-1.0MM")
      (footprint "eagle-import:CROWPI_POW_PAD-1.0MM")
      (libsource (lib "eagle-import") (part "CROWPI_POW_PADPAD-1.0MM"))
    )
    (comp (ref "P48")
      (value "PADPAD-1.0MM")
      (footprint "eagle-import:PAD-1.0MM")
      (libsource (lib "eagle-import") (part "PADPAD-1.0MM"))
    )
    (comp (ref "P49")
      (value "PADPAD-1.0MM")
      (footprint "eagle-import:PAD-1.0MM")
      (libsource (lib "eagle-import") (part "PADPAD-1.0MM"))
    )
    (comp (ref "P50")
      (value "CROWPI_POW_PADPAD-1.0MM")
      (footprint "eagle-import:CROWPI_POW_PAD-1.0MM")
      (libsource (lib "eagle-import") (part "CROWPI_POW_PADPAD-1.0MM"))
    )
    (comp (ref "P51")
      (value "CROWPI_POW_PADPAD-1.0MM")
      (footprint "eagle-import:CROWPI_POW_PAD-1.0MM")
      (libsource (lib "eagle-import") (part "CROWPI_POW_PADPAD-1.0MM"))
    )
    (comp (ref "P52")
      (value "CROWPI_POW_PADPAD-1.0MM")
      (footprint "eagle-import:CROWPI_POW_PAD-1.0MM")
      (libsource (lib "eagle-import") (part "CROWPI_POW_PADPAD-1.0MM"))
    )
    (comp (ref "P53")
      (value "CROWPI_POW_PADPAD-1.0MM")
      (footprint "eagle-import:CROWPI_POW_PAD-1.0MM")
      (libsource (lib "eagle-import") (part "CROWPI_POW_PADPAD-1.0MM"))
    )
    (comp (ref "P54")
      (value "CROWPI_POW_PADPAD-1.0MM")
      (footprint "eagle-import:CROWPI_POW_PAD-1.0MM")
      (libsource (lib "eagle-import") (part "CROWPI_POW_PADPAD-1.0MM"))
    )
    (comp (ref "P55")
      (value "CROWPI_POW_PADPAD-1.0MM")
      (footprint "eagle-import:CROWPI_POW_PAD-1.0MM")
      (libsource (lib "eagle-import") (part "CROWPI_POW_PADPAD-1.0MM"))
    )
    (comp (ref "P56")
      (value "CROWPI_POW_PADPAD-1.0MM")
      (footprint "eagle-import:CROWPI_POW_PAD-1.0MM")
      (libsource (lib "eagle-import") (part "CROWPI_POW_PADPAD-1.0MM"))
    )
    (comp (ref "P57")
      (value "CROWPI_POW_PADPAD-1.0MM")
      (footprint "eagle-import:CROWPI_POW_PAD-1.0MM")
      (libsource (lib "eagle-import") (part "CROWPI_POW_PADPAD-1.0MM"))
    )
    (comp (ref "P58")
      (value "CROWPI_POW_PADPAD-1.0MM")
      (footprint "eagle-import:CROWPI_POW_PAD-1.0MM")
      (libsource (lib "eagle-import") (part "CROWPI_POW_PADPAD-1.0MM"))
    )
    (comp (ref "P59")
      (value "CROWPI_POW_PADPAD-1.0MM")
      (footprint "eagle-import:CROWPI_POW_PAD-1.0MM")
      (libsource (lib "eagle-import") (part "CROWPI_POW_PADPAD-1.0MM"))
    )
    (comp (ref "P60")
      (value "CROWPI_POW_PADPAD-1.0MM")
      (footprint "eagle-import:CROWPI_POW_PAD-1.0MM")
      (libsource (lib "eagle-import") (part "CROWPI_POW_PADPAD-1.0MM"))
    )
    (comp (ref "P61")
      (value "CROWPI_POW_PADPAD-1.0MM")
      (footprint "eagle-import:CROWPI_POW_PAD-1.0MM")
      (libsource (lib "eagle-import") (part "CROWPI_POW_PADPAD-1.0MM"))
    )
    (comp (ref "P62")
      (value "CROWPI_POW_PADPAD-1.0MM")
      (footprint "eagle-import:CROWPI_POW_PAD-1.0MM")
      (libsource (lib "eagle-import") (part "CROWPI_POW_PADPAD-1.0MM"))
    )
    (comp (ref "P63")
      (value "CROWPI_POW_PADPAD-1.0MM")
      (footprint "eagle-import:CROWPI_POW_PAD-1.0MM")
      (libsource (lib "eagle-import") (part "CROWPI_POW_PADPAD-1.0MM"))
    )
    (comp (ref "Q1")
      (value "HXY2102EI")
      (footprint "eagle-import:SOT-323_W")
      (libsource (lib "eagle-import") (part "HXY2102EI"))
    )
    (comp (ref "Q2")
      (value "HXY2102EI")
      (footprint "eagle-import:SOT-323_W")
      (libsource (lib "eagle-import") (part "HXY2102EI"))
    )
    (comp (ref "Q19")
      (value "PMOS-3401-4A")
      (footprint "eagle-import:SOT-23")
      (libsource (lib "eagle-import") (part "P-MOS-SOT23"))
    )
    (comp (ref "R1")
      (value "10K")
      (footprint "eagle-import:DISCRETE_R0603")
      (libsource (lib "eagle-import") (part "Lora_RA-08H_Dev_DISCRETE_R-0603"))
    )
    (comp (ref "R2")
      (value "1K")
      (footprint "eagle-import:DISCRETE_R0603")
      (libsource (lib "eagle-import") (part "Lora_RA-08H_Dev_DISCRETE_R-0603"))
    )
    (comp (ref "R3")
      (value "4.7K")
      (footprint "eagle-import:DISCRETE_R0603")
      (libsource (lib "eagle-import") (part "Crowtail-_LED-V2.0-20190615-01_DISCRETE_R-0603"))
    )
    (comp (ref "R4")
      (value "3R")
      (footprint "eagle-import:DISCRETE_R0603")
      (libsource (lib "eagle-import") (part "Lora_RA-08H_Dev_DISCRETE_R-0603"))
    )
    (comp (ref "R5")
      (value "0R")
      (footprint "eagle-import:DISCRETE_R0603")
      (libsource (lib "eagle-import") (part "Lora_RA-08H_Dev_DISCRETE_R-0603"))
    )
    (comp (ref "R6")
      (value "1K")
      (footprint "eagle-import:DISCRETE_R0603")
      (libsource (lib "eagle-import") (part "Lora_RA-08H_Dev_DISCRETE_R-0603"))
    )
    (comp (ref "R7")
      (value "10K")
      (footprint "eagle-import:DISCRETE_R0603")
      (libsource (lib "eagle-import") (part "Lora_RA-08H_Dev_DISCRETE_R-0603"))
    )
    (comp (ref "R8")
      (value "10K/NC")
      (footprint "eagle-import:DISCRETE_R0603")
      (libsource (lib "eagle-import") (part "DISCRETE_R-0603"))
    )
    (comp (ref "R9")
      (value "0R 5%")
      (footprint "eagle-import:DISCRETE_R0603")
      (libsource (lib "eagle-import") (part "Lora_RA-08H_Dev_DISCRETE_R-0603"))
    )
    (comp (ref "R12")
      (value "5.1K")
      (footprint "eagle-import:DISCRETE_R0603")
      (libsource (lib "eagle-import") (part "Lora_RA-08H_Dev_DISCRETE_R-0603"))
    )
    (comp (ref "R13")
      (value "5.1K")
      (footprint "eagle-import:DISCRETE_R0603")
      (libsource (lib "eagle-import") (part "Lora_RA-08H_Dev_DISCRETE_R-0603"))
    )
    (comp (ref "R14")
      (value "10K/NC")
      (footprint "eagle-import:DISCRETE_R0603")
      (libsource (lib "eagle-import") (part "DISCRETE_R-0603"))
    )
    (comp (ref "R15")
      (value "NC")
      (footprint "eagle-import:DISCRETE_R0603")
      (libsource (lib "eagle-import") (part "Crowtail-_LED-V2.0-20190615-01_DISCRETE_R-0603"))
    )
    (comp (ref "R16")
      (value "0R")
      (footprint "eagle-import:DISCRETE_R0603")
      (libsource (lib "eagle-import") (part "Crowtail-_LED-V2.0-20190615-01_DISCRETE_R-0603"))
    )
    (comp (ref "R17")
      (value "10K")
      (footprint "eagle-import:DISCRETE_R0603")
      (libsource (lib "eagle-import") (part "Crowtail-_LED-V2.0-20190615-01_DISCRETE_R-0603"))
    )
    (comp (ref "R18")
      (value "NC")
      (footprint "eagle-import:DISCRETE_R0603")
      (libsource (lib "eagle-import") (part "Crowtail-_LED-V2.0-20190615-01_DISCRETE_R-0603"))
    )
    (comp (ref "R19")
      (value "100K1%")
      (footprint "eagle-import:DISCRETE_R0603")
      (libsource (lib "eagle-import") (part "DISCRETE_R-0603"))
    )
    (comp (ref "R20")
      (value "100K1%")
      (footprint "eagle-import:DISCRETE_R0603")
      (libsource (lib "eagle-import") (part "DISCRETE_R-0603"))
    )
    (comp (ref "R21")
      (value "10K")
      (footprint "eagle-import:DISCRETE_R0603")
      (libsource (lib "eagle-import") (part "Crowtail-_LED-V2.0-20190615-01_DISCRETE_R-0603"))
    )
    (comp (ref "R22")
      (value "NC")
      (footprint "eagle-import:DISCRETE_R0603")
      (libsource (lib "eagle-import") (part "Crowtail-_LED-V2.0-20190615-01_DISCRETE_R-0603"))
    )
    (comp (ref "R23")
      (value "10K/NC")
      (footprint "eagle-import:DISCRETE_R0603")
      (libsource (lib "eagle-import") (part "DISCRETE_R-0603"))
    )
    (comp (ref "R24")
      (value "1K")
      (footprint "eagle-import:DISCRETE_R0603")
      (libsource (lib "eagle-import") (part "Crowtail-_LED-V2.0-20190615-01_DISCRETE_R-0603"))
    )
    (comp (ref "R25")
      (value "1K")
      (footprint "eagle-import:DISCRETE_R0603")
      (libsource (lib "eagle-import") (part "Crowtail-_LED-V2.0-20190615-01_DISCRETE_R-0603"))
    )
    (comp (ref "R26")
      (value "4.7K")
      (footprint "eagle-import:DISCRETE_R0603")
      (libsource (lib "eagle-import") (part "Crowtail-_LED-V2.0-20190615-01_DISCRETE_R-0603"))
    )
    (comp (ref "R27")
      (value "3R")
      (footprint "eagle-import:DISCRETE_R0603")
      (libsource (lib "eagle-import") (part "Crowtail-_LED-V2.0-20190615-01_DISCRETE_R-0603"))
    )
    (comp (ref "R35")
      (value "4.7K")
      (footprint "eagle-import:DISCRETE_R0603")
      (libsource (lib "eagle-import") (part "Lora_RA-08H_Dev_DISCRETE_R-0603"))
    )
    (comp (ref "R36")
      (value "10K")
      (footprint "eagle-import:DISCRETE_R0603")
      (libsource (lib "eagle-import") (part "Crowtail-_LED-V2.0-20190615-01_DISCRETE_R-0603"))
    )
    (comp (ref "R37")
      (value "10K")
      (footprint "eagle-import:DISCRETE_R0603")
      (libsource (lib "eagle-import") (part "Crowtail-_LED-V2.0-20190615-01_DISCRETE_R-0603"))
    )
    (comp (ref "R38")
      (value "10K")
      (footprint "eagle-import:DISCRETE_R0603")
      (libsource (lib "eagle-import") (part "Crowtail-_LED-V2.0-20190615-01_DISCRETE_R-0603"))
    )
    (comp (ref "R39")
      (value "10K")
      (footprint "eagle-import:DISCRETE_R0603")
      (libsource (lib "eagle-import") (part "Crowtail-_LED-V2.0-20190615-01_DISCRETE_R-0603"))
    )
    (comp (ref "R40")
      (value "10K")
      (footprint "eagle-import:DISCRETE_R0603")
      (libsource (lib "eagle-import") (part "Crowtail-_LED-V2.0-20190615-01_DISCRETE_R-0603"))
    )
    (comp (ref "R66")
      (value "10K")
      (footprint "eagle-import:DISCRETE_R0603")
      (libsource (lib "eagle-import") (part "DISCRETE_R-0603"))
    )
    (comp (ref "R68")
      (value "5.1K")
      (footprint "eagle-import:DISCRETE_R0603")
      (libsource (lib "eagle-import") (part "Crowtail-_LED-V2.0-20190615-01_DISCRETE_R-0603"))
    )
    (comp (ref "R69")
      (value "5.1K")
      (footprint "eagle-import:DISCRETE_R0603")
      (libsource (lib "eagle-import") (part "Crowtail-_LED-V2.0-20190615-01_DISCRETE_R-0603"))
    )
    (comp (ref "R70")
      (value "0R")
      (footprint "eagle-import:DISCRETE_R0603")
      (libsource (lib "eagle-import") (part "Crowtail-_LED-V2.0-20190615-01_DISCRETE_R-0603"))
    )
    (comp (ref "R81")
      (value "45.3K 1%")
      (footprint "eagle-import:DISCRETE_R0603")
      (libsource (lib "eagle-import") (part "Lora_RA-08H_Dev_DISCRETE_R-0603"))
    )
    (comp (ref "R82")
      (value "10K 1%")
      (footprint "eagle-import:DISCRETE_R0603")
      (libsource (lib "eagle-import") (part "Lora_RA-08H_Dev_DISCRETE_R-0603"))
    )
    (comp (ref "R83")
      (value "0R")
      (footprint "eagle-import:DISCRETE_R0603")
      (libsource (lib "eagle-import") (part "Crowtail-_LED-V2.0-20190615-01_DISCRETE_R-0603"))
    )
    (comp (ref "R84")
      (value "2K")
      (footprint "eagle-import:DISCRETE_R0603")
      (libsource (lib "eagle-import") (part "DISCRETE_R-0603"))
    )
    (comp (ref "R85")
      (value "4.7K")
      (footprint "eagle-import:DISCRETE_R0603")
      (libsource (lib "eagle-import") (part "Lora_RA-08H_Dev_DISCRETE_R-0603"))
    )
    (comp (ref "R105")
      (value "10K")
      (footprint "eagle-import:DISCRETE_R0603")
      (libsource (lib "eagle-import") (part "DISCRETE_R-0603"))
    )
    (comp (ref "SD1")
      (value "HOLDER-MICROSD-9P")
      (footprint "eagle-import:9P-SMD-W_-RING")
      (libsource (lib "eagle-import") (part "HOLDER-MICROSD-9P"))
    )
    (comp (ref "SW1")
      (value "KEY-6")
      (footprint "eagle-import:KEY-6")
      (libsource (lib "eagle-import") (part "KEY-6"))
    )
    (comp (ref "SW2")
      (value "KEY-6")
      (footprint "eagle-import:KEY-6")
      (libsource (lib "eagle-import") (part "KEY-6"))
    )
    (comp (ref "T1")
      (value "3M-5")
      (footprint "eagle-import:3M-5")
      (libsource (lib "eagle-import") (part "3M-5"))
    )
    (comp (ref "T2")
      (value "3M-5")
      (footprint "eagle-import:3M-5")
      (libsource (lib "eagle-import") (part "3M-5"))
    )
    (comp (ref "T3")
      (value "3M-5")
      (footprint "eagle-import:3M-5")
      (libsource (lib "eagle-import") (part "3M-5"))
    )
    (comp (ref "T4")
      (value "3M-5")
      (footprint "eagle-import:3M-5")
      (libsource (lib "eagle-import") (part "3M-5"))
    )
    (comp (ref "U1")
      (value "RP2040_RP2040")
      (footprint "eagle-import:RP2040_QFN-56")
      (libsource (lib "eagle-import") (part "RP2040_RP2040"))
    )
    (comp (ref "U2")
      (value "SELF_W25Q128JV")
      (footprint "eagle-import:SELF_SOIC-8-208MIL")
      (libsource (lib "eagle-import") (part "SELF_W25Q128JV"))
    )
    (comp (ref "U3")
      (value "XPT2046")
      (footprint "eagle-import:XP2046-SSOP16")
      (libsource (lib "eagle-import") (part "XPT2046"))
    )
    (comp (ref "U5")
      (value "4054A")
      (footprint "eagle-import:SOP23-5")
      (libsource (lib "eagle-import") (part "4054A"))
    )
    (comp (ref "U6")
      (value "HM3416H")
      (footprint "eagle-import:CROWBOT_-V1.0-20220525_A_XBJ_SOT23-5")
      (libsource (lib "eagle-import") (part "CROWBOT_-V1.0-20220525_A_XBJ_HM3420B"))
    )
    (comp (ref "U7")
      (value "CH340X")
      (footprint "eagle-import:MSOP-10_W")
      (libsource (lib "eagle-import") (part "CH340E"))
    )
    (comp (ref "X1")
      (value "12MHZ_SMD3225")
      (footprint "eagle-import:A_XBJ_SMD3225")
      (libsource (lib "eagle-import") (part "A_XBJ_XTAL"))
    )
  )
  (nets
    (net (code "1") (name "+1V1") (class "Default")
      (node (ref "C13") (pin "1") (pinfunction "1_1") (pintype "passive"))
      (node (ref "C14") (pin "1") (pinfunction "1_1") (pintype "passive"))
      (node (ref "U1") (pin "23") (pinfunction "VDD_1V1_23") (pintype "bidirectional"))
      (node (ref "U1") (pin "45") (pinfunction "LDO_OUT_45") (pintype "bidirectional"))
      (node (ref "U1") (pin "50") (pinfunction "VDD_1V1_50") (pintype "bidirectional"))
    )
    (net (code "2") (name "+3V3") (class "Default")
      (node (ref "C10") (pin "1") (pinfunction "1_1") (pintype "passive"))
      (node (ref "C11") (pin "1") (pinfunction "1_1") (pintype "passive"))
      (node (ref "C12") (pin "1") (pinfunction "1_1") (pintype "passive"))
      (node (ref "C15") (pin "2") (pinfunction "2_2") (pintype "passive"))
      (node (ref "C17") (pin "1") (pinfunction "1_1") (pintype "passive"))
      (node (ref "C18") (pin "2") (pinfunction "2_2") (pintype "passive"))
      (node (ref "C20") (pin "1") (pinfunction "1_1") (pintype "passive"))
      (node (ref "C21") (pin "1") (pinfunction "1_1") (pintype "passive"))
      (node (ref "C28") (pin "2") (pinfunction "2_2") (pintype "passive"))
      (node (ref "C33") (pin "2") (pinfunction "2_2") (pintype "passive"))
      (node (ref "C35") (pin "1") (pinfunction "1_1") (pintype "passive"))
      (node (ref "C42") (pin "2") (pinfunction "2_2") (pintype "passive"))
      (node (ref "C43") (pin "1") (pinfunction "1_1") (pintype "passive"))
      (node (ref "C5") (pin "1") (pinfunction "1_1") (pintype "passive"))
      (node (ref "C6") (pin "1") (pinfunction "1_1") (pintype "passive"))
      (node (ref "C7") (pin "1") (pinfunction "1_1") (pintype "passive"))
      (node (ref "C9") (pin "1") (pinfunction "1_1") (pintype "passive"))
      (node (ref "J1") (pin "3") (pinfunction "3_3") (pintype "bidirectional"))
      (node (ref "J17") (pin "6") (pinfunction "IOVCC_6") (pintype "bidirectional"))
      (node (ref "J17") (pin "7") (pinfunction "VDD_7") (pintype "bidirectional"))
      (node (ref "J2") (pin "16") (pinfunction "P$16_16") (pintype "bidirectional"))
      (node (ref "J6") (pin "3") (pinfunction "3_3") (pintype "bidirectional"))
      (node (ref "L4") (pin "2") (pinfunction "P$2_2") (pintype "bidirectional"))
      (node (ref "P10") (pin "P$1") (pinfunction "P$1_P$1") (pintype "bidirectional"))
      (node (ref "P13") (pin "P$1") (pinfunction "P$1_P$1") (pintype "bidirectional"))
      (node (ref "P22") (pin "P$1") (pinfunction "P$1_P$1") (pintype "bidirectional"))
      (node (ref "P30") (pin "P$1") (pinfunction "P$1_P$1") (pintype "bidirectional"))
      (node (ref "P43") (pin "P$1") (pinfunction "P$1_P$1") (pintype "bidirectional"))
      (node (ref "R1") (pin "2") (pinfunction "2_2") (pintype "passive"))
      (node (ref "R105") (pin "2") (pinfunction "2_2") (pintype "passive"))
      (node (ref "R15") (pin "2") (pinfunction "2_2") (pintype "passive"))
      (node (ref "R17") (pin "2") (pinfunction "2_2") (pintype "passive"))
      (node (ref "R21") (pin "2") (pinfunction "2_2") (pintype "passive"))
      (node (ref "R23") (pin "1") (pinfunction "1_1") (pintype "passive"))
      (node (ref "R24") (pin "2") (pinfunction "2_2") (pintype "passive"))
      (node (ref "R25") (pin "2") (pinfunction "2_2") (pintype "passive"))
      (node (ref "R26") (pin "2") (pinfunction "2_2") (pintype "passive"))
      (node (ref "R27") (pin "2") (pinfunction "2_2") (pintype "passive"))
      (node (ref "R3") (pin "2") (pinfunction "2_2") (pintype "passive"))
      (node (ref "R35") (pin "2") (pinfunction "2_2") (pintype "passive"))
      (node (ref "R36") (pin "1") (pinfunction "1_1") (pintype "passive"))
      (node (ref "R37") (pin "1") (pinfunction "1_1") (pintype "passive"))
      (node (ref "R38") (pin "1") (pinfunction "1_1") (pintype "passive"))
      (node (ref "R39") (pin "1") (pinfunction "1_1") (pintype "passive"))
      (node (ref "R4") (pin "2") (pinfunction "2_2") (pintype "passive"))
      (node (ref "R40") (pin "1") (pinfunction "1_1") (pintype "passive"))
      (node (ref "R5") (pin "2") (pinfunction "2_2") (pintype "passive"))
      (node (ref "R7") (pin "2") (pinfunction "2_2") (pintype "passive"))
      (node (ref "R81") (pin "1") (pinfunction "1_1") (pintype "passive"))
      (node (ref "R85") (pin "2") (pinfunction "2_2") (pintype "passive"))
      (node (ref "SD1") (pin "4") (pinfunction "VDD_4") (pintype "bidirectional"))
      (node (ref "U1") (pin "1") (pinfunction "VDDIO_1") (pintype "bidirectional"))
      (node (ref "U1") (pin "10") (pinfunction "VDDIO_10") (pintype "bidirectional"))
      (node (ref "U1") (pin "22") (pinfunction "VDDIO_22") (pintype "bidirectional"))
      (node (ref "U1") (pin "33") (pinfunction "VDDIO_33") (pintype "bidirectional"))
      (node (ref "U1") (pin "42") (pinfunction "VDDIO_42") (pintype "bidirectional"))
      (node (ref "U1") (pin "44") (pinfunction "LDO_IN_44") (pintype "bidirectional"))
      (node (ref "U1") (pin "48") (pinfunction "USB_VDD_48") (pintype "bidirectional"))
      (node (ref "U1") (pin "49") (pinfunction "VDDIO_49") (pintype "bidirectional"))
      (node (ref "U2") (pin "8") (pinfunction "VCC_8") (pintype "bidirectional"))
      (node (ref "U3") (pin "1") (pinfunction "VCC_1") (pintype "bidirectional"))
      (node (ref "U3") (pin "10") (pinfunction "IOVDD_10") (pintype "bidirectional"))
      (node (ref "U3") (pin "9") (pinfunction "VREF_9") (pintype "bidirectional"))
      (node (ref "U7") (pin "10") (pinfunction "V3_10") (pintype "bidirectional"))
      (node (ref "U7") (pin "7") (pinfunction "VCC_7") (pintype "bidirectional"))
    )
    (net (code "3") (name "+5V_UART0") (class "Default")
      (node (ref "D4") (pin "1") (pinfunction "1_1") (pintype "bidirectional"))
      (node (ref "D8") (pin "1") (pinfunction "1_1") (pintype "bidirectional"))
      (node (ref "J15") (pin "A4") (pinfunction "VBUS_A4") (pintype "bidirectional"))
      (node (ref "J15") (pin "A9") (pinfunction "VBUS_A9") (pintype "bidirectional"))
      (node (ref "J15") (pin "B4") (pinfunction "VBUS_B4") (pintype "bidirectional"))
      (node (ref "J15") (pin "B9") (pinfunction "VBUS_B9") (pintype "bidirectional"))
      (node (ref "P26") (pin "P$1") (pinfunction "P$1_P$1") (pintype "bidirectional"))
    )
    (net (code "4") (name "+5V_USB") (class "Default")
      (node (ref "D5") (pin "1") (pinfunction "1_1") (pintype "bidirectional"))
      (node (ref "D6") (pin "1") (pinfunction "1_1") (pintype "bidirectional"))
      (node (ref "J14") (pin "A4") (pinfunction "VBUS_A4") (pintype "bidirectional"))
      (node (ref "J14") (pin "A9") (pinfunction "VBUS_A9") (pintype "bidirectional"))
      (node (ref "J14") (pin "B4") (pinfunction "VBUS_B4") (pintype "bidirectional"))
      (node (ref "J14") (pin "B9") (pinfunction "VBUS_B9") (pintype "bidirectional"))
      (node (ref "P2") (pin "P$1") (pinfunction "P$1_P$1") (pintype "bidirectional"))
    )
    (net (code "5") (name "/CHG_LED") (class "Default")
      (node (ref "D15") (pin "-") (pinfunction "-_-") (pintype "passive"))
      (node (ref "U5") (pin "1") (pinfunction "GHRG_1") (pintype "bidirectional"))
    )
    (net (code "6") (name "/IM0") (class "Default")
      (node (ref "J17") (pin "38") (pinfunction "IM0_38") (pintype "bidirectional"))
      (node (ref "P60") (pin "P$1") (pinfunction "P$1_P$1") (pintype "bidirectional"))
      (node (ref "R15") (pin "1") (pinfunction "1_1") (pintype "passive"))
      (node (ref "R16") (pin "2") (pinfunction "2_2") (pintype "passive"))
    )
    (net (code "7") (name "/IM1") (class "Default")
      (node (ref "J17") (pin "39") (pinfunction "IM1_39") (pintype "bidirectional"))
      (node (ref "P61") (pin "P$1") (pinfunction "P$1_P$1") (pintype "bidirectional"))
      (node (ref "R17") (pin "1") (pinfunction "1_1") (pintype "passive"))
      (node (ref "R18") (pin "2") (pinfunction "2_2") (pintype "passive"))
    )
    (net (code "8") (name "/IM2") (class "Default")
      (node (ref "J17") (pin "40") (pinfunction "IM2_40") (pintype "bidirectional"))
      (node (ref "P62") (pin "P$1") (pinfunction "P$1_P$1") (pintype "bidirectional"))
      (node (ref "R21") (pin "1") (pinfunction "1_1") (pintype "passive"))
      (node (ref "R22") (pin "2") (pinfunction "2_2") (pintype "passive"))
    )
    (net (code "9") (name "/VBAT_IN") (class "Default")
      (node (ref "C22") (pin "2") (pinfunction "2_2") (pintype "bidirectional"))
      (node (ref "C23") (pin "1") (pinfunction "1_1") (pintype "passive"))
      (node (ref "D4") (pin "2") (pinfunction "2_2") (pintype "bidirectional"))
      (node (ref "D6") (pin "2") (pinfunction "2_2") (pintype "bidirectional"))
      (node (ref "Q19") (pin "1") (pinfunction "G_1") (pintype "bidirectional"))
      (node (ref "R66") (pin "2") (pinfunction "2_2") (pintype "passive"))
      (node (ref "U5") (pin "4") (pinfunction "VCC_4") (pintype "bidirectional"))
    )
    (net (code "10") (name "/VIN") (class "Default")
      (node (ref "C31") (pin "2") (pinfunction "2_2") (pintype "passive"))
      (node (ref "C32") (pin "1") (pinfunction "1_1") (pintype "passive"))
      (node (ref "D2") (pin "-") (pinfunction "2_-") (pintype "bidirectional"))
      (node (ref "D5") (pin "2") (pinfunction "2_2") (pintype "bidirectional"))
      (node (ref "D8") (pin "2") (pinfunction "2_2") (pintype "bidirectional"))
      (node (ref "Q19") (pin "2") (pinfunction "S_2") (pintype "bidirectional"))
      (node (ref "U6") (pin "1") (pinfunction "EN_1") (pintype "bidirectional"))
      (node (ref "U6") (pin "4") (pinfunction "VIN_4") (pintype "bidirectional"))
    )
    (net (code "11") (name "AVDD") (class "Default")
      (node (ref "C3") (pin "1") (pinfunction "1_1") (pintype "passive"))
      (node (ref "R5") (pin "1") (pinfunction "1_1") (pintype "passive"))
      (node (ref "U1") (pin "43") (pinfunction "ADC_VDD_43") (pintype "bidirectional"))
    )
    (net (code "12") (name "BAT+") (class "Default")
      (node (ref "C19") (pin "2") (pinfunction "2_2") (pintype "passive"))
      (node (ref "D2") (pin "+") (pinfunction "1_+") (pintype "bidirectional"))
      (node (ref "J16") (pin "P$1") (pinfunction "P$1_P$1") (pintype "bidirectional"))
      (node (ref "P7") (pin "P$1") (pinfunction "P$1_P$1") (pintype "bidirectional"))
      (node (ref "Q19") (pin "3") (pinfunction "D_3") (pintype "bidirectional"))
      (node (ref "R20") (pin "1") (pinfunction "1_1") (pintype "passive"))
      (node (ref "U5") (pin "3") (pinfunction "BAT_3") (pintype "bidirectional"))
    )
    (net (code "13") (name "BOOT") (class "Default")
      (node (ref "R6") (pin "2") (pinfunction "2_2") (pintype "passive"))
      (node (ref "SW2") (pin "2") (pinfunction "2_2") (pintype "bidirectional"))
    )
    (net (code "14") (name "GND") (class "Default")
      (node (ref "C1") (pin "2") (pinfunction "2_2") (pintype "passive"))
      (node (ref "C10") (pin "2") (pinfunction "2_2") (pintype "passive"))
      (node (ref "C11") (pin "2") (pinfunction "2_2") (pintype "passive"))
      (node (ref "C12") (pin "2") (pinfunction "2_2") (pintype "passive"))
      (node (ref "C13") (pin "2") (pinfunction "2_2") (pintype "passive"))
      (node (ref "C14") (pin "2") (pinfunction "2_2") (pintype "passive"))
      (node (ref "C15") (pin "1") (pinfunction "1_1") (pintype "passive"))
      (node (ref "C17") (pin "2") (pinfunction "2_2") (pintype "passive"))
      (node (ref "C18") (pin "1") (pinfunction "1_1") (pintype "passive"))
      (node (ref "C19") (pin "1") (pinfunction "1_1") (pintype "passive"))
      (node (ref "C2") (pin "1") (pinfunction "1_1") (pintype "passive"))
      (node (ref "C20") (pin "2") (pinfunction "2_2") (pintype "passive"))
      (node (ref "C21") (pin "2") (pinfunction "2_2") (pintype "passive"))
      (node (ref "C22") (pin "1") (pinfunction "1_1") (pintype "bidirectional"))
      (node (ref "C23") (pin "2") (pinfunction "2_2") (pintype "passive"))
      (node (ref "C28") (pin "1") (pinfunction "1_1") (pintype "passive"))
      (node (ref "C3") (pin "2") (pinfunction "2_2") (pintype "passive"))
      (node (ref "C30") (pin "1") (pinfunction "1_1") (pintype "passive"))
      (node (ref "C31") (pin "1") (pinfunction "1_1") (pintype "passive"))
      (node (ref "C32") (pin "2") (pinfunction "2_2") (pintype "passive"))
      (node (ref "C33") (pin "1") (pinfunction "1_1") (pintype "passive"))
      (node (ref "C35") (pin "2") (pinfunction "2_2") (pintype "passive"))
      (node (ref "C38") (pin "1") (pinfunction "1_1") (pintype "passive"))
      (node (ref "C39") (pin "1") (pinfunction "1_1") (pintype "passive"))
      (node (ref "C4") (pin "2") (pinfunction "2_2") (pintype "passive"))
      (node (ref "C40") (pin "1") (pinfunction "1_1") (pintype "passive"))
      (node (ref "C42") (pin "1") (pinfunction "1_1") (pintype "passive"))
      (node (ref "C43") (pin "2") (pinfunction "2_2") (pintype "passive"))
      (node (ref "C5") (pin "2") (pinfunction "2_2") (pintype "passive"))
      (node (ref "C6") (pin "2") (pinfunction "2_2") (pintype "passive"))
      (node (ref "C7") (pin "2") (pinfunction "2_2") (pintype "passive"))
      (node (ref "C9") (pin "2") (pinfunction "2_2") (pintype "passive"))
      (node (ref "D3") (pin "-") (pinfunction "-_-") (pintype "passive"))
      (node (ref "J1") (pin "4") (pinfunction "4_4") (pintype "bidirectional"))
      (node (ref "J1") (pin "SS1") (pinfunction "SS1_SS1") (pintype "bidirectional"))
      (node (ref "J1") (pin "SS2") (pinfunction "SS2_SS2") (pintype "bidirectional"))
      (node (ref "J14") (pin "A1") (pinfunction "GND_A1") (pintype "bidirectional"))
      (node (ref "J14") (pin "A12") (pinfunction "GND_A12") (pintype "bidirectional"))
      (node (ref "J14") (pin "B1") (pinfunction "GND_B1") (pintype "bidirectional"))
      (node (ref "J14") (pin "B12") (pinfunction "GND_B12") (pintype "bidirectional"))
      (node (ref "J14") (pin "P$6") (pinfunction "P$17_P$6") (pintype "bidirectional"))
      (node (ref "J14") (pin "P$7") (pinfunction "P$18_P$7") (pintype "bidirectional"))
      (node (ref "J14") (pin "P$8") (pinfunction "P$19_P$8") (pintype "bidirectional"))
      (node (ref "J14") (pin "P$9") (pinfunction "P$20_P$9") (pintype "bidirectional"))
      (node (ref "J15") (pin "A1") (pinfunction "GND_A1") (pintype "bidirectional"))
      (node (ref "J15") (pin "A12") (pinfunction "GND_A12") (pintype "bidirectional"))
      (node (ref "J15") (pin "B1") (pinfunction "GND_B1") (pintype "bidirectional"))
      (node (ref "J15") (pin "B12") (pinfunction "GND_B12") (pintype "bidirectional"))
      (node (ref "J15") (pin "P$6") (pinfunction "P$17_P$6") (pintype "bidirectional"))
      (node (ref "J15") (pin "P$7") (pinfunction "P$18_P$7") (pintype "bidirectional"))
      (node (ref "J15") (pin "P$8") (pinfunction "P$19_P$8") (pintype "bidirectional"))
      (node (ref "J15") (pin "P$9") (pinfunction "P$20_P$9") (pintype "bidirectional"))
      (node (ref "J16") (pin "P$2") (pinfunction "P$2_P$2") (pintype "bidirectional"))
      (node (ref "J16") (pin "P$3") (pinfunction "P$3_P$3") (pintype "bidirectional"))
      (node (ref "J16") (pin "P$4") (pinfunction "P$4_P$4") (pintype "bidirectional"))
      (node (ref "J17") (pin "16") (pinfunction "GND2_16") (pintype "bidirectional"))
      (node (ref "J17") (pin "37") (pinfunction "GND3_37") (pintype "bidirectional"))
      (node (ref "J17") (pin "5") (pinfunction "GND1_5") (pintype "bidirectional"))
      (node (ref "J2") (pin "15") (pinfunction "P$15_15") (pintype "bidirectional"))
      (node (ref "J6") (pin "4") (pinfunction "4_4") (pintype "bidirectional"))
      (node (ref "J6") (pin "SS1") (pinfunction "SS1_SS1") (pintype "bidirectional"))
      (node (ref "J6") (pin "SS2") (pinfunction "SS2_SS2") (pintype "bidirectional"))
      (node (ref "P1") (pin "P$1") (pinfunction "P$1_P$1") (pintype "bidirectional"))
      (node (ref "P14") (pin "P$1") (pinfunction "P$1_P$1") (pintype "bidirectional"))
      (node (ref "P21") (pin "P$1") (pinfunction "P$1_P$1") (pintype "bidirectional"))
      (node (ref "P25") (pin "P$1") (pinfunction "P$1_P$1") (pintype "bidirectional"))
      (node (ref "P29") (pin "P$1") (pinfunction "P$1_P$1") (pintype "bidirectional"))
      (node (ref "P42") (pin "P$1") (pinfunction "P$1_P$1") (pintype "bidirectional"))
      (node (ref "P59") (pin "P$1") (pinfunction "P$1_P$1") (pintype "bidirectional"))
      (node (ref "P6") (pin "P$1") (pinfunction "P$1_P$1") (pintype "bidirectional"))
      (node (ref "P9") (pin "P$1") (pinfunction "P$1_P$1") (pintype "bidirectional"))
      (node (ref "Q1") (pin "2") (pinfunction "S_2") (pintype "bidirectional"))
      (node (ref "Q2") (pin "2") (pinfunction "S_2") (pintype "bidirectional"))
      (node (ref "R12") (pin "2") (pinfunction "2_2") (pintype "passive"))
      (node (ref "R13") (pin "1") (pinfunction "1_1") (pintype "passive"))
      (node (ref "R14") (pin "1") (pinfunction "1_1") (pintype "passive"))
      (node (ref "R16") (pin "1") (pinfunction "1_1") (pintype "passive"))
      (node (ref "R18") (pin "1") (pinfunction "1_1") (pintype "passive"))
      (node (ref "R19") (pin "2") (pinfunction "2_2") (pintype "passive"))
      (node (ref "R22") (pin "1") (pinfunction "1_1") (pintype "passive"))
      (node (ref "R66") (pin "1") (pinfunction "1_1") (pintype "passive"))
      (node (ref "R68") (pin "2") (pinfunction "2_2") (pintype "passive"))
      (node (ref "R69") (pin "1") (pinfunction "1_1") (pintype "passive"))
      (node (ref "R8") (pin "1") (pinfunction "1_1") (pintype "passive"))
      (node (ref "R82") (pin "1") (pinfunction "1_1") (pintype "passive"))
      (node (ref "R84") (pin "2") (pinfunction "2_2") (pintype "passive"))
      (node (ref "SD1") (pin "6") (pinfunction "VSS_6") (pintype "bidirectional"))
      (node (ref "SD1") (pin "G1") (pinfunction "G1_G1") (pintype "bidirectional"))
      (node (ref "SD1") (pin "G2") (pinfunction "G2_G2") (pintype "bidirectional"))
      (node (ref "SD1") (pin "G3") (pinfunction "G3_G3") (pintype "bidirectional"))
      (node (ref "SD1") (pin "G4") (pinfunction "G4_G4") (pintype "bidirectional"))
      (node (ref "SW1") (pin "1") (pinfunction "1_1") (pintype "bidirectional"))
      (node (ref "SW2") (pin "1") (pinfunction "1_1") (pintype "bidirectional"))
      (node (ref "T1") (pin "1") (pinfunction "P$1_1") (pintype "bidirectional"))
      (node (ref "T2") (pin "1") (pinfunction "P$1_1") (pintype "bidirectional"))
      (node (ref "T3") (pin "1") (pinfunction "P$1_1") (pintype "bidirectional"))
      (node (ref "T4") (pin "1") (pinfunction "P$1_1") (pintype "bidirectional"))
      (node (ref "U1") (pin "19") (pinfunction "TESTEN_19") (pintype "bidirectional"))
      (node (ref "U1") (pin "EPAD") (pinfunction "GND_EPAD") (pintype "bidirectional"))
      (node (ref "U2") (pin "4") (pinfunction "GND_4") (pintype "bidirectional"))
      (node (ref "U3") (pin "6") (pinfunction "GND_6") (pintype "bidirectional"))
      (node (ref "U5") (pin "2") (pinfunction "GND_2") (pintype "bidirectional"))
      (node (ref "U6") (pin "2") (pinfunction "GND_2") (pintype "bidirectional"))
      (node (ref "U7") (pin "3") (pinfunction "GND_3") (pintype "bidirectional"))
      (node (ref "X1") (pin "2") (pinfunction "GND_2") (pintype "bidirectional"))
      (node (ref "X1") (pin "4") (pinfunction "GND_4") (pintype "bidirectional"))
    )
    (net (code "15") (name "GP0{slash}UART0_TX") (class "Default")
      (node (ref "J2") (pin "1") (pinfunction "P$1_1") (pintype "bidirectional"))
      (node (ref "P8") (pin "P$1") (pinfunction "P$1_P$1") (pintype "bidirectional"))
      (node (ref "R70") (pin "2") (pinfunction "2_2") (pintype "passive"))
      (node (ref "U1") (pin "2") (pinfunction "GPIO0_2") (pintype "bidirectional"))
    )
    (net (code "16") (name "GP1{slash}UART0_RX") (class "Default")
      (node (ref "J2") (pin "2") (pinfunction "P$2_2") (pintype "bidirectional"))
      (node (ref "P17") (pin "P$1") (pinfunction "P$1_P$1") (pintype "bidirectional"))
      (node (ref "R83") (pin "2") (pinfunction "2_2") (pintype "passive"))
      (node (ref "U1") (pin "3") (pinfunction "GPIO1_3") (pintype "bidirectional"))
    )
    (net (code "17") (name "GP2{slash}I2C1_SDA") (class "Default")
      (node (ref "J2") (pin "3") (pinfunction "P$3_3") (pintype "bidirectional"))
      (node (ref "P18") (pin "P$1") (pinfunction "P$1_P$1") (pintype "bidirectional"))
      (node (ref "U1") (pin "4") (pinfunction "GPIO2_4") (pintype "bidirectional"))
    )
    (net (code "18") (name "GP3{slash}I2C1_SCL") (class "Default")
      (node (ref "J2") (pin "4") (pinfunction "P$4_4") (pintype "bidirectional"))
      (node (ref "P19") (pin "P$1") (pinfunction "P$1_P$1") (pintype "bidirectional"))
      (node (ref "U1") (pin "5") (pinfunction "GPIO3_5") (pintype "bidirectional"))
    )
    (net (code "19") (name "GP4{slash}UART1_TX") (class "Default")
      (node (ref "J1") (pin "2") (pinfunction "2_2") (pintype "bidirectional"))
      (node (ref "J2") (pin "5") (pinfunction "P$5_5") (pintype "bidirectional"))
      (node (ref "P20") (pin "P$1") (pinfunction "P$1_P$1") (pintype "bidirectional"))
      (node (ref "P23") (pin "P$1") (pinfunction "P$1_P$1") (pintype "bidirectional"))
      (node (ref "U1") (pin "6") (pinfunction "GPIO4_6") (pintype "bidirectional"))
    )
    (net (code "20") (name "GP5{slash}UART1_RX") (class "Default")
      (node (ref "J1") (pin "1") (pinfunction "1_1") (pintype "bidirectional"))
      (node (ref "J2") (pin "6") (pinfunction "P$6_6") (pintype "bidirectional"))
      (node (ref "P24") (pin "P$1") (pinfunction "P$1_P$1") (pintype "bidirectional"))
      (node (ref "P50") (pin "P$1") (pinfunction "P$1_P$1") (pintype "bidirectional"))
      (node (ref "U1") (pin "7") (pinfunction "GPIO5_7") (pintype "bidirectional"))
    )
    (net (code "21") (name "GP6*I2C1_SDA") (class "Default")
      (node (ref "J2") (pin "7") (pinfunction "P$7_7") (pintype "bidirectional"))
      (node (ref "P51") (pin "P$1") (pinfunction "P$1_P$1") (pintype "bidirectional"))
      (node (ref "U1") (pin "8") (pinfunction "GPIO6_8") (pintype "bidirectional"))
    )
    (net (code "22") (name "GP7*I2C1_SCL") (class "Default")
      (node (ref "J2") (pin "8") (pinfunction "P$8_8") (pintype "bidirectional"))
      (node (ref "P52") (pin "P$1") (pinfunction "P$1_P$1") (pintype "bidirectional"))
      (node (ref "U1") (pin "9") (pinfunction "GPIO7_9") (pintype "bidirectional"))
    )
    (net (code "23") (name "GP8{slash}LCD_DC") (class "Default")
      (node (ref "J17") (pin "11") (pinfunction "WR_11") (pintype "bidirectional"))
      (node (ref "P34") (pin "P$1") (pinfunction "P$1_P$1") (pintype "bidirectional"))
      (node (ref "U1") (pin "11") (pinfunction "GPIO8_11") (pintype "bidirectional"))
    )
    (net (code "24") (name "GP9{slash}LCD_CS{slash}SPI_CS0") (class "Default")
      (node (ref "J17") (pin "9") (pinfunction "CS_9") (pintype "bidirectional"))
      (node (ref "P35") (pin "P$1") (pinfunction "P$1_P$1") (pintype "bidirectional"))
      (node (ref "U1") (pin "12") (pinfunction "GPIO9_12") (pintype "bidirectional"))
    )
    (net (code "25") (name "GP10{slash}SPI_CLK{slash}LCD_CLK{slash}TP_CLK{slash}SD_CLK") (class "Default")
      (node (ref "J17") (pin "10") (pinfunction "RS_10") (pintype "bidirectional"))
      (node (ref "P32") (pin "P$1") (pinfunction "P$1_P$1") (pintype "bidirectional"))
      (node (ref "P45") (pin "P$1") (pinfunction "P$1_P$1") (pintype "bidirectional"))
      (node (ref "R25") (pin "1") (pinfunction "1_1") (pintype "passive"))
      (node (ref "SD1") (pin "5") (pinfunction "SCLK_5") (pintype "bidirectional"))
      (node (ref "U1") (pin "13") (pinfunction "GPIO10_13") (pintype "bidirectional"))
      (node (ref "U3") (pin "16") (pinfunction "DCLK_16") (pintype "bidirectional"))
    )
    (net (code "26") (name "GP11{slash}SPI_MOSI{slash}LCD_SDI{slash}TP_SDI{slash}SD_SDI") (class "Default")
      (node (ref "J17") (pin "13") (pinfunction "SDA_13") (pintype "bidirectional"))
      (node (ref "P36") (pin "P$1") (pinfunction "P$1_P$1") (pintype "bidirectional"))
      (node (ref "P44") (pin "P$1") (pinfunction "P$1_P$1") (pintype "bidirectional"))
      (node (ref "R24") (pin "1") (pinfunction "1_1") (pintype "passive"))
      (node (ref "R39") (pin "2") (pinfunction "2_2") (pintype "passive"))
      (node (ref "SD1") (pin "3") (pinfunction "DI_3") (pintype "bidirectional"))
      (node (ref "U1") (pin "14") (pinfunction "GPIO11_14") (pintype "bidirectional"))
      (node (ref "U3") (pin "14") (pinfunction "DIN_14") (pintype "bidirectional"))
    )
    (net (code "27") (name "GP12{slash}SPI_MISO{slash}LCD_SDO{slash}TP_SDO{slash}SD_SDO") (class "Default")
      (node (ref "P46") (pin "P$1") (pinfunction "P$1_P$1") (pintype "bidirectional"))
      (node (ref "R40") (pin "2") (pinfunction "2_2") (pintype "passive"))
      (node (ref "SD1") (pin "7") (pinfunction "DO_7") (pintype "bidirectional"))
      (node (ref "U1") (pin "15") (pinfunction "GPIO12_15") (pintype "bidirectional"))
      (node (ref "U3") (pin "12") (pinfunction "DOUT_12") (pintype "bidirectional"))
    )
    (net (code "28") (name "GP13{slash}LCD_BL") (class "Default")
      (node (ref "U1") (pin "16") (pinfunction "GPIO13_16") (pintype "bidirectional"))
    )
    (net (code "29") (name "GP14{slash}BUZZER") (class "Default")
      (node (ref "Q2") (pin "1") (pinfunction "G_1") (pintype "bidirectional"))
      (node (ref "R14") (pin "2") (pinfunction "2_2") (pintype "passive"))
      (node (ref "U1") (pin "17") (pinfunction "GPIO14_17") (pintype "bidirectional"))
    )
    (net (code "30") (name "GP15{slash}LCD_RST") (class "Default")
      (node (ref "J17") (pin "15") (pinfunction "REST_15") (pintype "bidirectional"))
      (node (ref "P5") (pin "P$1") (pinfunction "P$1_P$1") (pintype "bidirectional"))
      (node (ref "U1") (pin "18") (pinfunction "GPIO15_18") (pintype "bidirectional"))
    )
    (net (code "31") (name "GP16{slash}TP_CS{slash}SPI_CS1") (class "Default")
      (node (ref "U1") (pin "27") (pinfunction "GPIO16_27") (pintype "bidirectional"))
      (node (ref "U3") (pin "15") (pinfunction "CS_15") (pintype "bidirectional"))
    )
    (net (code "32") (name "GP17{slash}TP_IRQ") (class "Default")
      (node (ref "R105") (pin "1") (pinfunction "1_1") (pintype "passive"))
      (node (ref "U1") (pin "28") (pinfunction "GPIO17_28") (pintype "bidirectional"))
      (node (ref "U3") (pin "11") (pinfunction "PENIRQ_11") (pintype "bidirectional"))
    )
    (net (code "33") (name "GP18{slash}LCD_BL_PWM") (class "Default")
      (node (ref "Q1") (pin "1") (pinfunction "G_1") (pintype "bidirectional"))
      (node (ref "R8") (pin "2") (pinfunction "2_2") (pintype "passive"))
      (node (ref "U1") (pin "29") (pinfunction "GPIO18_29") (pintype "bidirectional"))
    )
    (net (code "34") (name "GP19*") (class "Default")
      (node (ref "J2") (pin "9") (pinfunction "P$9_9") (pintype "bidirectional"))
      (node (ref "P53") (pin "P$1") (pinfunction "P$1_P$1") (pintype "bidirectional"))
      (node (ref "U1") (pin "30") (pinfunction "GPIO19_30") (pintype "bidirectional"))
    )
    (net (code "35") (name "GP20{slash}I2C0_SDA") (class "Default")
      (node (ref "J2") (pin "10") (pinfunction "P$10_10") (pintype "bidirectional"))
      (node (ref "J6") (pin "2") (pinfunction "2_2") (pintype "bidirectional"))
      (node (ref "P15") (pin "P$1") (pinfunction "P$1_P$1") (pintype "bidirectional"))
      (node (ref "P54") (pin "P$1") (pinfunction "P$1_P$1") (pintype "bidirectional"))
      (node (ref "R3") (pin "1") (pinfunction "1_1") (pintype "passive"))
      (node (ref "U1") (pin "31") (pinfunction "GPIO20_31") (pintype "bidirectional"))
    )
    (net (code "36") (name "GP21{slash}I2C0_SCL") (class "Default")
      (node (ref "J2") (pin "11") (pinfunction "P$11_11") (pintype "bidirectional"))
      (node (ref "J6") (pin "1") (pinfunction "1_1") (pintype "bidirectional"))
      (node (ref "P16") (pin "P$1") (pinfunction "P$1_P$1") (pintype "bidirectional"))
      (node (ref "P55") (pin "P$1") (pinfunction "P$1_P$1") (pintype "bidirectional"))
      (node (ref "R26") (pin "1") (pinfunction "1_1") (pintype "passive"))
      (node (ref "U1") (pin "32") (pinfunction "GPIO21_32") (pintype "bidirectional"))
    )
    (net (code "37") (name "GP22{slash}SD_CS{slash}SPI_CS2") (class "Default")
      (node (ref "P47") (pin "P$1") (pinfunction "P$1_P$1") (pintype "bidirectional"))
      (node (ref "R36") (pin "2") (pinfunction "2_2") (pintype "passive"))
      (node (ref "SD1") (pin "2") (pinfunction "CS_2") (pintype "bidirectional"))
      (node (ref "U1") (pin "34") (pinfunction "GPIO22_34") (pintype "bidirectional"))
    )
    (net (code "38") (name "GP23*") (class "Default")
      (node (ref "U1") (pin "35") (pinfunction "GPIO23_35") (pintype "bidirectional"))
    )
    (net (code "39") (name "GP24*") (class "Default")
      (node (ref "U1") (pin "36") (pinfunction "GPIO24_36") (pintype "bidirectional"))
    )
    (net (code "40") (name "GP25{slash}LED") (class "Default")
      (node (ref "U1") (pin "37") (pinfunction "GPIO25_37") (pintype "bidirectional"))
    )
    (net (code "41") (name "GP26*ADC0*I2C1_SDA") (class "Default")
      (node (ref "J2") (pin "12") (pinfunction "P$12_12") (pintype "bidirectional"))
      (node (ref "P56") (pin "P$1") (pinfunction "P$1_P$1") (pintype "bidirectional"))
      (node (ref "U1") (pin "38") (pinfunction "GPIO26/ADC0_38") (pintype "bidirectional"))
    )
    (net (code "42") (name "GP27*ADC1*I2C1_SCL") (class "Default")
      (node (ref "J2") (pin "13") (pinfunction "P$13_13") (pintype "bidirectional"))
      (node (ref "P57") (pin "P$1") (pinfunction "P$1_P$1") (pintype "bidirectional"))
      (node (ref "U1") (pin "39") (pinfunction "GPIO27/ADC1_39") (pintype "bidirectional"))
    )
    (net (code "43") (name "GP28*ADC2") (class "Default")
      (node (ref "J2") (pin "14") (pinfunction "P$14_14") (pintype "bidirectional"))
      (node (ref "P58") (pin "P$1") (pinfunction "P$1_P$1") (pintype "bidirectional"))
      (node (ref "U1") (pin "40") (pinfunction "GPIO28/ADC2_40") (pintype "bidirectional"))
    )
    (net (code "44") (name "GP29{slash}BAT+_ADC3") (class "Default")
      (node (ref "R19") (pin "1") (pinfunction "1_1") (pintype "passive"))
      (node (ref "R20") (pin "2") (pinfunction "2_2") (pintype "passive"))
      (node (ref "U1") (pin "41") (pinfunction "GPIO29/ADC3_41") (pintype "bidirectional"))
    )
    (net (code "45") (name "LED-K") (class "Default")
      (node (ref "J17") (pin "34") (pinfunction "LEDK1_34") (pintype "bidirectional"))
      (node (ref "J17") (pin "35") (pinfunction "LEDK2_35") (pintype "bidirectional"))
      (node (ref "J17") (pin "36") (pinfunction "LEDK3_36") (pintype "bidirectional"))
      (node (ref "P41") (pin "P$1") (pinfunction "P$1_P$1") (pintype "bidirectional"))
      (node (ref "R9") (pin "2") (pinfunction "2_2") (pintype "passive"))
    )
    (net (code "46") (name "LED_A") (class "Default")
      (node (ref "J17") (pin "33") (pinfunction "LEDA_33") (pintype "bidirectional"))
      (node (ref "P63") (pin "P$1") (pinfunction "P$1_P$1") (pintype "bidirectional"))
      (node (ref "R27") (pin "1") (pinfunction "1_1") (pintype "passive"))
    )
    (net (code "47") (name "Net-(B1-+)") (class "Default")
      (node (ref "B1") (pin "1") (pinfunction "+_1") (pintype "bidirectional"))
      (node (ref "D1") (pin "-") (pinfunction "2_-") (pintype "bidirectional"))
      (node (ref "R4") (pin "1") (pinfunction "1_1") (pintype "passive"))
    )
    (net (code "48") (name "Net-(B1--)") (class "Default")
      (node (ref "B1") (pin "2") (pinfunction "-_2") (pintype "bidirectional"))
      (node (ref "D1") (pin "+") (pinfunction "1_+") (pintype "bidirectional"))
      (node (ref "Q2") (pin "3") (pinfunction "D_3") (pintype "bidirectional"))
    )
    (net (code "49") (name "Net-(D3-Pad+)") (class "Default")
      (node (ref "D3") (pin "+") (pinfunction "+_+") (pintype "passive"))
      (node (ref "R35") (pin "1") (pinfunction "1_1") (pintype "passive"))
    )
    (net (code "50") (name "Net-(D15-Pad+)") (class "Default")
      (node (ref "D15") (pin "+") (pinfunction "+_+") (pintype "passive"))
      (node (ref "R85") (pin "1") (pinfunction "1_1") (pintype "passive"))
    )
    (net (code "51") (name "Net-(J14-CC1)") (class "Default")
      (node (ref "J14") (pin "A5") (pinfunction "CC1_A5") (pintype "bidirectional"))
      (node (ref "R13") (pin "2") (pinfunction "2_2") (pintype "passive"))
    )
    (net (code "52") (name "Net-(J14-CC2)") (class "Default")
      (node (ref "J14") (pin "B5") (pinfunction "CC2_B5") (pintype "bidirectional"))
      (node (ref "R12") (pin "1") (pinfunction "1_1") (pintype "passive"))
    )
    (net (code "53") (name "Net-(J15-CC1)") (class "Default")
      (node (ref "J15") (pin "A5") (pinfunction "CC1_A5") (pintype "bidirectional"))
      (node (ref "R69") (pin "2") (pinfunction "2_2") (pintype "passive"))
    )
    (net (code "54") (name "Net-(J15-CC2)") (class "Default")
      (node (ref "J15") (pin "B5") (pinfunction "CC2_B5") (pintype "bidirectional"))
      (node (ref "R68") (pin "1") (pinfunction "1_1") (pintype "passive"))
    )
    (net (code "55") (name "Net-(L4-P$1)") (class "Default")
      (node (ref "L4") (pin "1") (pinfunction "P$1_1") (pintype "bidirectional"))
      (node (ref "U6") (pin "3") (pinfunction "SW_3") (pintype "bidirectional"))
    )
    (net (code "56") (name "Net-(Q1-D)") (class "Default")
      (node (ref "Q1") (pin "3") (pinfunction "D_3") (pintype "bidirectional"))
      (node (ref "R9") (pin "1") (pinfunction "1_1") (pintype "passive"))
    )
    (net (code "57") (name "Net-(SD1-DATA1)") (class "Default")
      (node (ref "R38") (pin "2") (pinfunction "2_2") (pintype "passive"))
      (node (ref "SD1") (pin "8") (pinfunction "DATA1_8") (pintype "bidirectional"))
    )
    (net (code "58") (name "Net-(SD1-DATA2)") (class "Default")
      (node (ref "R37") (pin "2") (pinfunction "2_2") (pintype "passive"))
      (node (ref "SD1") (pin "1") (pinfunction "DATA2_1") (pintype "bidirectional"))
    )
    (net (code "59") (name "Net-(U1-XIN)") (class "Default")
      (node (ref "C1") (pin "1") (pinfunction "1_1") (pintype "passive"))
      (node (ref "U1") (pin "20") (pinfunction "XIN_20") (pintype "bidirectional"))
      (node (ref "X1") (pin "1") (pinfunction "XIN_1") (pintype "bidirectional"))
    )
    (net (code "60") (name "Net-(U1-XOUT)") (class "Default")
      (node (ref "R2") (pin "2") (pinfunction "2_2") (pintype "passive"))
      (node (ref "U1") (pin "21") (pinfunction "XOUT_21") (pintype "bidirectional"))
    )
    (net (code "61") (name "Net-(U3-VBAT)") (class "Default")
      (node (ref "R23") (pin "2") (pinfunction "2_2") (pintype "passive"))
      (node (ref "U3") (pin "7") (pinfunction "VBAT_7") (pintype "bidirectional"))
    )
    (net (code "62") (name "Net-(U5-PROG)") (class "Default")
      (node (ref "R84") (pin "1") (pinfunction "1_1") (pintype "passive"))
      (node (ref "U5") (pin "5") (pinfunction "PROG_5") (pintype "bidirectional"))
    )
    (net (code "63") (name "Net-(U6-FB)") (class "Default")
      (node (ref "R81") (pin "2") (pinfunction "2_2") (pintype "passive"))
      (node (ref "R82") (pin "2") (pinfunction "2_2") (pintype "passive"))
      (node (ref "U6") (pin "5") (pinfunction "FB_5") (pintype "bidirectional"))
    )
    (net (code "64") (name "Net-(U7-RXD)") (class "Default")
      (node (ref "R70") (pin "1") (pinfunction "1_1") (pintype "passive"))
      (node (ref "U7") (pin "9") (pinfunction "RXD_9") (pintype "bidirectional"))
    )
    (net (code "65") (name "Net-(U7-TXD)") (class "Default")
      (node (ref "R83") (pin "1") (pinfunction "1_1") (pintype "passive"))
      (node (ref "U7") (pin "8") (pinfunction "TXD_8") (pintype "bidirectional"))
    )
    (net (code "66") (name "Net-(X1-XOUT)") (class "Default")
      (node (ref "C2") (pin "2") (pinfunction "2_2") (pintype "passive"))
      (node (ref "R2") (pin "1") (pinfunction "1_1") (pintype "passive"))
      (node (ref "X1") (pin "3") (pinfunction "XOUT_3") (pintype "bidirectional"))
    )
    (net (code "67") (name "QSPI_CS") (class "Default")
      (node (ref "R6") (pin "1") (pinfunction "1_1") (pintype "passive"))
      (node (ref "R7") (pin "1") (pinfunction "1_1") (pintype "passive"))
      (node (ref "U1") (pin "56") (pinfunction "QSPI_~{CS}_56") (pintype "bidirectional"))
      (node (ref "U2") (pin "1") (pinfunction "/CS_1") (pintype "bidirectional"))
    )
    (net (code "68") (name "QSPI_D0") (class "Default")
      (node (ref "U1") (pin "53") (pinfunction "QSPI_SD0_53") (pintype "bidirectional"))
      (node (ref "U2") (pin "5") (pinfunction "DI(IO0)_5") (pintype "bidirectional"))
    )
    (net (code "69") (name "QSPI_D1") (class "Default")
      (node (ref "U1") (pin "55") (pinfunction "QSPI_SD1_55") (pintype "bidirectional"))
      (node (ref "U2") (pin "2") (pinfunction "DO(IO1)_2") (pintype "bidirectional"))
    )
    (net (code "70") (name "QSPI_D2") (class "Default")
      (node (ref "U1") (pin "54") (pinfunction "QSPI_SD2_54") (pintype "bidirectional"))
      (node (ref "U2") (pin "3") (pinfunction "/WP(IO2)_3") (pintype "bidirectional"))
    )
    (net (code "71") (name "QSPI_D3") (class "Default")
      (node (ref "U1") (pin "51") (pinfunction "QSPI_SD3_51") (pintype "bidirectional"))
      (node (ref "U2") (pin "7") (pinfunction "/HOLD/RESET(IO3)_7") (pintype "bidirectional"))
    )
    (net (code "72") (name "QSPI_SCK") (class "Default")
      (node (ref "U1") (pin "52") (pinfunction "QSPI_SCLK_52") (pintype "bidirectional"))
      (node (ref "U2") (pin "6") (pinfunction "CLK_6") (pintype "bidirectional"))
    )
    (net (code "73") (name "RESET") (class "Default")
      (node (ref "C4") (pin "1") (pinfunction "1_1") (pintype "passive"))
      (node (ref "P31") (pin "P$1") (pinfunction "P$1_P$1") (pintype "bidirectional"))
      (node (ref "R1") (pin "1") (pinfunction "1_1") (pintype "passive"))
      (node (ref "SW1") (pin "2") (pinfunction "2_2") (pintype "bidirectional"))
      (node (ref "U1") (pin "26") (pinfunction "RUN_26") (pintype "bidirectional"))
    )
    (net (code "74") (name "SWCLK") (class "Default")
      (node (ref "P11") (pin "P$1") (pinfunction "P$1_P$1") (pintype "bidirectional"))
      (node (ref "U1") (pin "24") (pinfunction "SWCLK_24") (pintype "bidirectional"))
    )
    (net (code "75") (name "SWDIO") (class "Default")
      (node (ref "P12") (pin "P$1") (pinfunction "P$1_P$1") (pintype "bidirectional"))
      (node (ref "U1") (pin "25") (pinfunction "SWDIO_25") (pintype "bidirectional"))
    )
    (net (code "76") (name "TP_X+") (class "Default")
      (node (ref "C30") (pin "2") (pinfunction "2_2") (pintype "passive"))
      (node (ref "J17") (pin "1") (pinfunction "XL_1") (pintype "bidirectional"))
      (node (ref "P33") (pin "P$1") (pinfunction "P$1_P$1") (pintype "bidirectional"))
      (node (ref "U3") (pin "2") (pinfunction "XP_2") (pintype "bidirectional"))
    )
    (net (code "77") (name "TP_X-") (class "Default")
      (node (ref "C39") (pin "2") (pinfunction "2_2") (pintype "passive"))
      (node (ref "J17") (pin "3") (pinfunction "XR_3") (pintype "bidirectional"))
      (node (ref "P38") (pin "P$1") (pinfunction "P$1_P$1") (pintype "bidirectional"))
      (node (ref "U3") (pin "4") (pinfunction "XN_4") (pintype "bidirectional"))
    )
    (net (code "78") (name "TP_Y+") (class "Default")
      (node (ref "C38") (pin "2") (pinfunction "2_2") (pintype "passive"))
      (node (ref "J17") (pin "4") (pinfunction "YD_4") (pintype "bidirectional"))
      (node (ref "P39") (pin "P$1") (pinfunction "P$1_P$1") (pintype "bidirectional"))
      (node (ref "U3") (pin "3") (pinfunction "YP_3") (pintype "bidirectional"))
    )
    (net (code "79") (name "TP_Y-") (class "Default")
      (node (ref "C40") (pin "2") (pinfunction "2_2") (pintype "passive"))
      (node (ref "J17") (pin "2") (pinfunction "YU_2") (pintype "bidirectional"))
      (node (ref "P37") (pin "P$1") (pinfunction "P$1_P$1") (pintype "bidirectional"))
      (node (ref "U3") (pin "5") (pinfunction "YN_5") (pintype "bidirectional"))
    )
    (net (code "80") (name "UART_USB_D+") (class "Default")
      (node (ref "J15") (pin "A6") (pinfunction "DP1_A6") (pintype "bidirectional"))
      (node (ref "J15") (pin "B6") (pinfunction "DP2_B6") (pintype "bidirectional"))
      (node (ref "P27") (pin "P$1") (pinfunction "P$1_P$1") (pintype "bidirectional"))
      (node (ref "U7") (pin "1") (pinfunction "D+_1") (pintype "bidirectional"))
    )
    (net (code "81") (name "UART_USB_D-") (class "Default")
      (node (ref "J15") (pin "A7") (pinfunction "DN1_A7") (pintype "bidirectional"))
      (node (ref "J15") (pin "B7") (pinfunction "DN2_B7") (pintype "bidirectional"))
      (node (ref "P28") (pin "P$1") (pinfunction "P$1_P$1") (pintype "bidirectional"))
      (node (ref "U7") (pin "2") (pinfunction "D-_2") (pintype "bidirectional"))
    )
    (net (code "82") (name "USB_D+") (class "Default")
      (node (ref "J14") (pin "A6") (pinfunction "DP1_A6") (pintype "bidirectional"))
      (node (ref "J14") (pin "B6") (pinfunction "DP2_B6") (pintype "bidirectional"))
      (node (ref "P3") (pin "P$1") (pinfunction "P$1_P$1") (pintype "bidirectional"))
      (node (ref "U1") (pin "47") (pinfunction "USB_D+_47") (pintype "bidirectional"))
    )
    (net (code "83") (name "USB_D-") (class "Default")
      (node (ref "J14") (pin "A7") (pinfunction "DN1_A7") (pintype "bidirectional"))
      (node (ref "J14") (pin "B7") (pinfunction "DN2_B7") (pintype "bidirectional"))
      (node (ref "P4") (pin "P$1") (pinfunction "P$1_P$1") (pintype "bidirectional"))
      (node (ref "U1") (pin "46") (pinfunction "USB_D-_46") (pintype "bidirectional"))
    )
    (net (code "84") (name "unconnected-(J14-SBU1-PadA8)") (class "Default")
      (node (ref "J14") (pin "A8") (pinfunction "SBU1_A8") (pintype "bidirectional"))
    )
    (net (code "85") (name "unconnected-(J14-SBU2-PadB8)") (class "Default")
      (node (ref "J14") (pin "B8") (pinfunction "SBU2_B8") (pintype "bidirectional"))
    )
    (net (code "86") (name "unconnected-(J15-SBU1-PadA8)") (class "Default")
      (node (ref "J15") (pin "A8") (pinfunction "SBU1_A8") (pintype "bidirectional"))
    )
    (net (code "87") (name "unconnected-(J15-SBU2-PadB8)") (class "Default")
      (node (ref "J15") (pin "B8") (pinfunction "SBU2_B8") (pintype "bidirectional"))
    )
    (net (code "88") (name "unconnected-(J17-DB0-Pad17)") (class "Default")
      (node (ref "J17") (pin "17") (pinfunction "DB0_17") (pintype "bidirectional"))
    )
    (net (code "89") (name "unconnected-(J17-DB1-Pad18)") (class "Default")
      (node (ref "J17") (pin "18") (pinfunction "DB1_18") (pintype "bidirectional"))
    )
    (net (code "90") (name "unconnected-(J17-DB2-Pad19)") (class "Default")
      (node (ref "J17") (pin "19") (pinfunction "DB2_19") (pintype "bidirectional"))
    )
    (net (code "91") (name "unconnected-(J17-DB3-Pad20)") (class "Default")
      (node (ref "J17") (pin "20") (pinfunction "DB3_20") (pintype "bidirectional"))
    )
    (net (code "92") (name "unconnected-(J17-DB4-Pad21)") (class "Default")
      (node (ref "J17") (pin "21") (pinfunction "DB4_21") (pintype "bidirectional"))
    )
    (net (code "93") (name "unconnected-(J17-DB5-Pad22)") (class "Default")
      (node (ref "J17") (pin "22") (pinfunction "DB5_22") (pintype "bidirectional"))
    )
    (net (code "94") (name "unconnected-(J17-DB6-Pad23)") (class "Default")
      (node (ref "J17") (pin "23") (pinfunction "DB6_23") (pintype "bidirectional"))
    )
    (net (code "95") (name "unconnected-(J17-DB7-Pad24)") (class "Default")
      (node (ref "J17") (pin "24") (pinfunction "DB7_24") (pintype "bidirectional"))
    )
    (net (code "96") (name "unconnected-(J17-DB8-Pad25)") (class "Default")
      (node (ref "J17") (pin "25") (pinfunction "DB8_25") (pintype "bidirectional"))
    )
    (net (code "97") (name "unconnected-(J17-DB9-Pad26)") (class "Default")
      (node (ref "J17") (pin "26") (pinfunction "DB9_26") (pintype "bidirectional"))
    )
    (net (code "98") (name "unconnected-(J17-DB10-Pad27)") (class "Default")
      (node (ref "J17") (pin "27") (pinfunction "DB10_27") (pintype "bidirectional"))
    )
    (net (code "99") (name "unconnected-(J17-DB11-Pad28)") (class "Default")
      (node (ref "J17") (pin "28") (pinfunction "DB11_28") (pintype "bidirectional"))
    )
    (net (code "100") (name "unconnected-(J17-DB12-Pad29)") (class "Default")
      (node (ref "J17") (pin "29") (pinfunction "DB12_29") (pintype "bidirectional"))
    )
    (net (code "101") (name "unconnected-(J17-DB13-Pad30)") (class "Default")
      (node (ref "J17") (pin "30") (pinfunction "DB13_30") (pintype "bidirectional"))
    )
    (net (code "102") (name "unconnected-(J17-DB14-Pad31)") (class "Default")
      (node (ref "J17") (pin "31") (pinfunction "DB14_31") (pintype "bidirectional"))
    )
    (net (code "103") (name "unconnected-(J17-DB15-Pad32)") (class "Default")
      (node (ref "J17") (pin "32") (pinfunction "DB15_32") (pintype "bidirectional"))
    )
    (net (code "104") (name "unconnected-(J17-FMARK-Pad8)") (class "Default")
      (node (ref "J17") (pin "8") (pinfunction "FMARK_8") (pintype "bidirectional"))
    )
    (net (code "105") (name "unconnected-(J17-RD-Pad12)") (class "Default")
      (node (ref "J17") (pin "12") (pinfunction "RD_12") (pintype "bidirectional"))
    )
    (net (code "106") (name "unconnected-(J17-SDO-Pad14)") (class "Default")
      (node (ref "J17") (pin "14") (pinfunction "SDO_14") (pintype "bidirectional"))
    )
    (net (code "107") (name "unconnected-(P48-PadP$1)") (class "Default")
      (node (ref "P48") (pin "P$1") (pinfunction "P$1_P$1") (pintype "bidirectional"))
    )
    (net (code "108") (name "unconnected-(P49-PadP$1)") (class "Default")
      (node (ref "P49") (pin "P$1") (pinfunction "P$1_P$1") (pintype "bidirectional"))
    )
    (net (code "109") (name "unconnected-(SD1-CDN-Pad9)") (class "Default")
      (node (ref "SD1") (pin "9") (pinfunction "CDN_9") (pintype "bidirectional"))
    )
    (net (code "110") (name "unconnected-(U3-BUESY-Pad13)") (class "Default")
      (node (ref "U3") (pin "13") (pinfunction "BUESY_13") (pintype "bidirectional"))
    )
    (net (code "111") (name "unconnected-(U3-IN-Pad8)") (class "Default")
      (node (ref "U3") (pin "8") (pinfunction "IN_8") (pintype "bidirectional"))
    )
    (net (code "112") (name "unconnected-(U7-CTS-Pad5)") (class "Default")
      (node (ref "U7") (pin "5") (pinfunction "CTS_5") (pintype "bidirectional"))
    )
    (net (code "113") (name "unconnected-(U7-RTS-Pad4)") (class "Default")
      (node (ref "U7") (pin "4") (pinfunction "RTS_4") (pintype "bidirectional"))
    )
    (net (code "114") (name "unconnected-(U7-TNOW-Pad6)") (class "Default")
      (node (ref "U7") (pin "6") (pinfunction "TNOW_6") (pintype "bidirectional"))
    )
  )
)
